# stm_v0_6.net
KiCad netlist of a schematic drawn in EAGLE
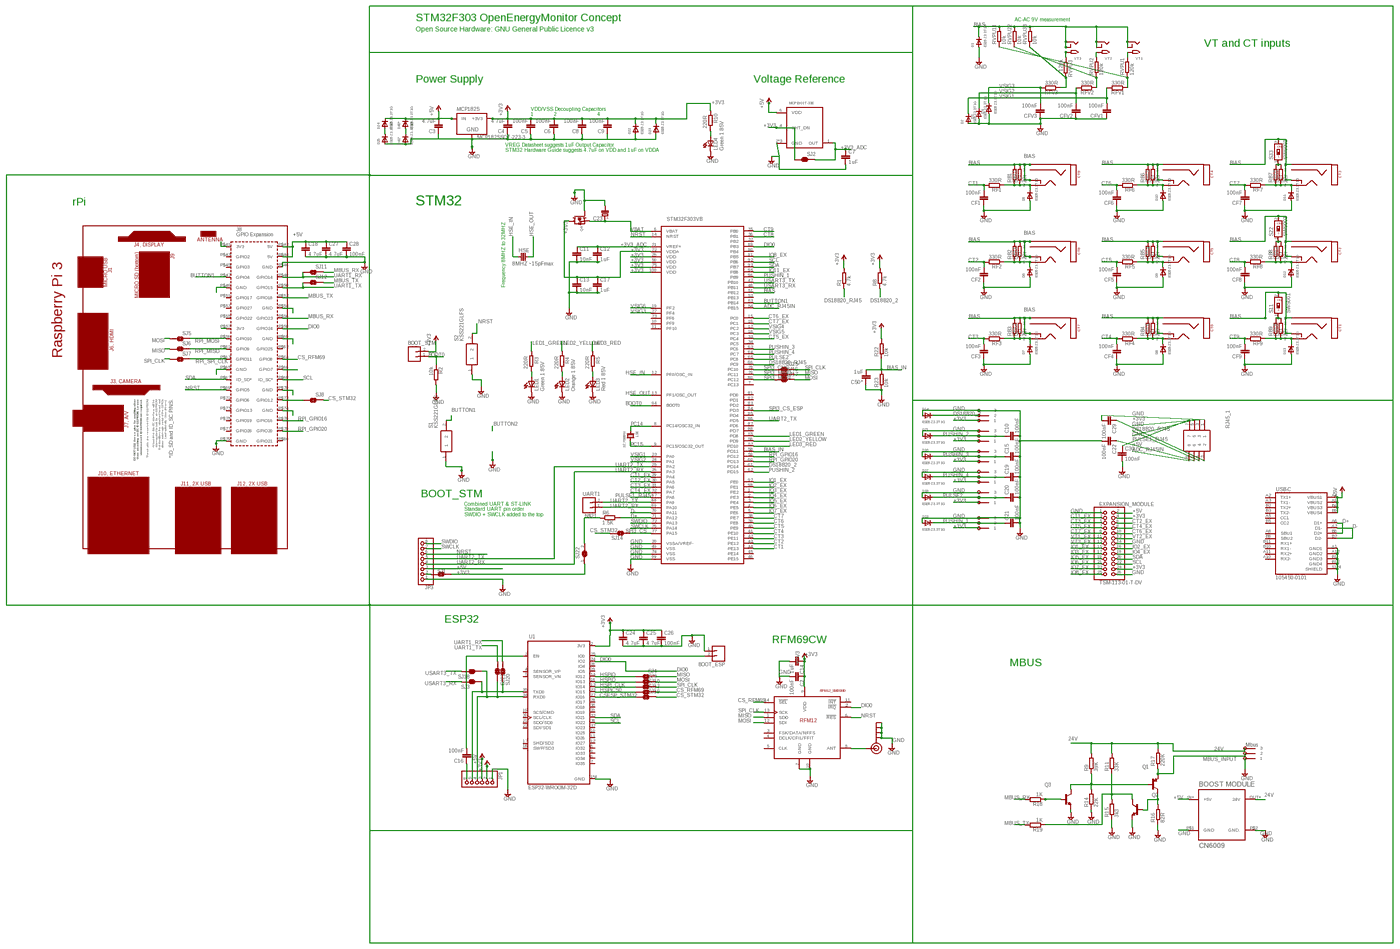
[diagram p0: schematic, sheet 1, overview]
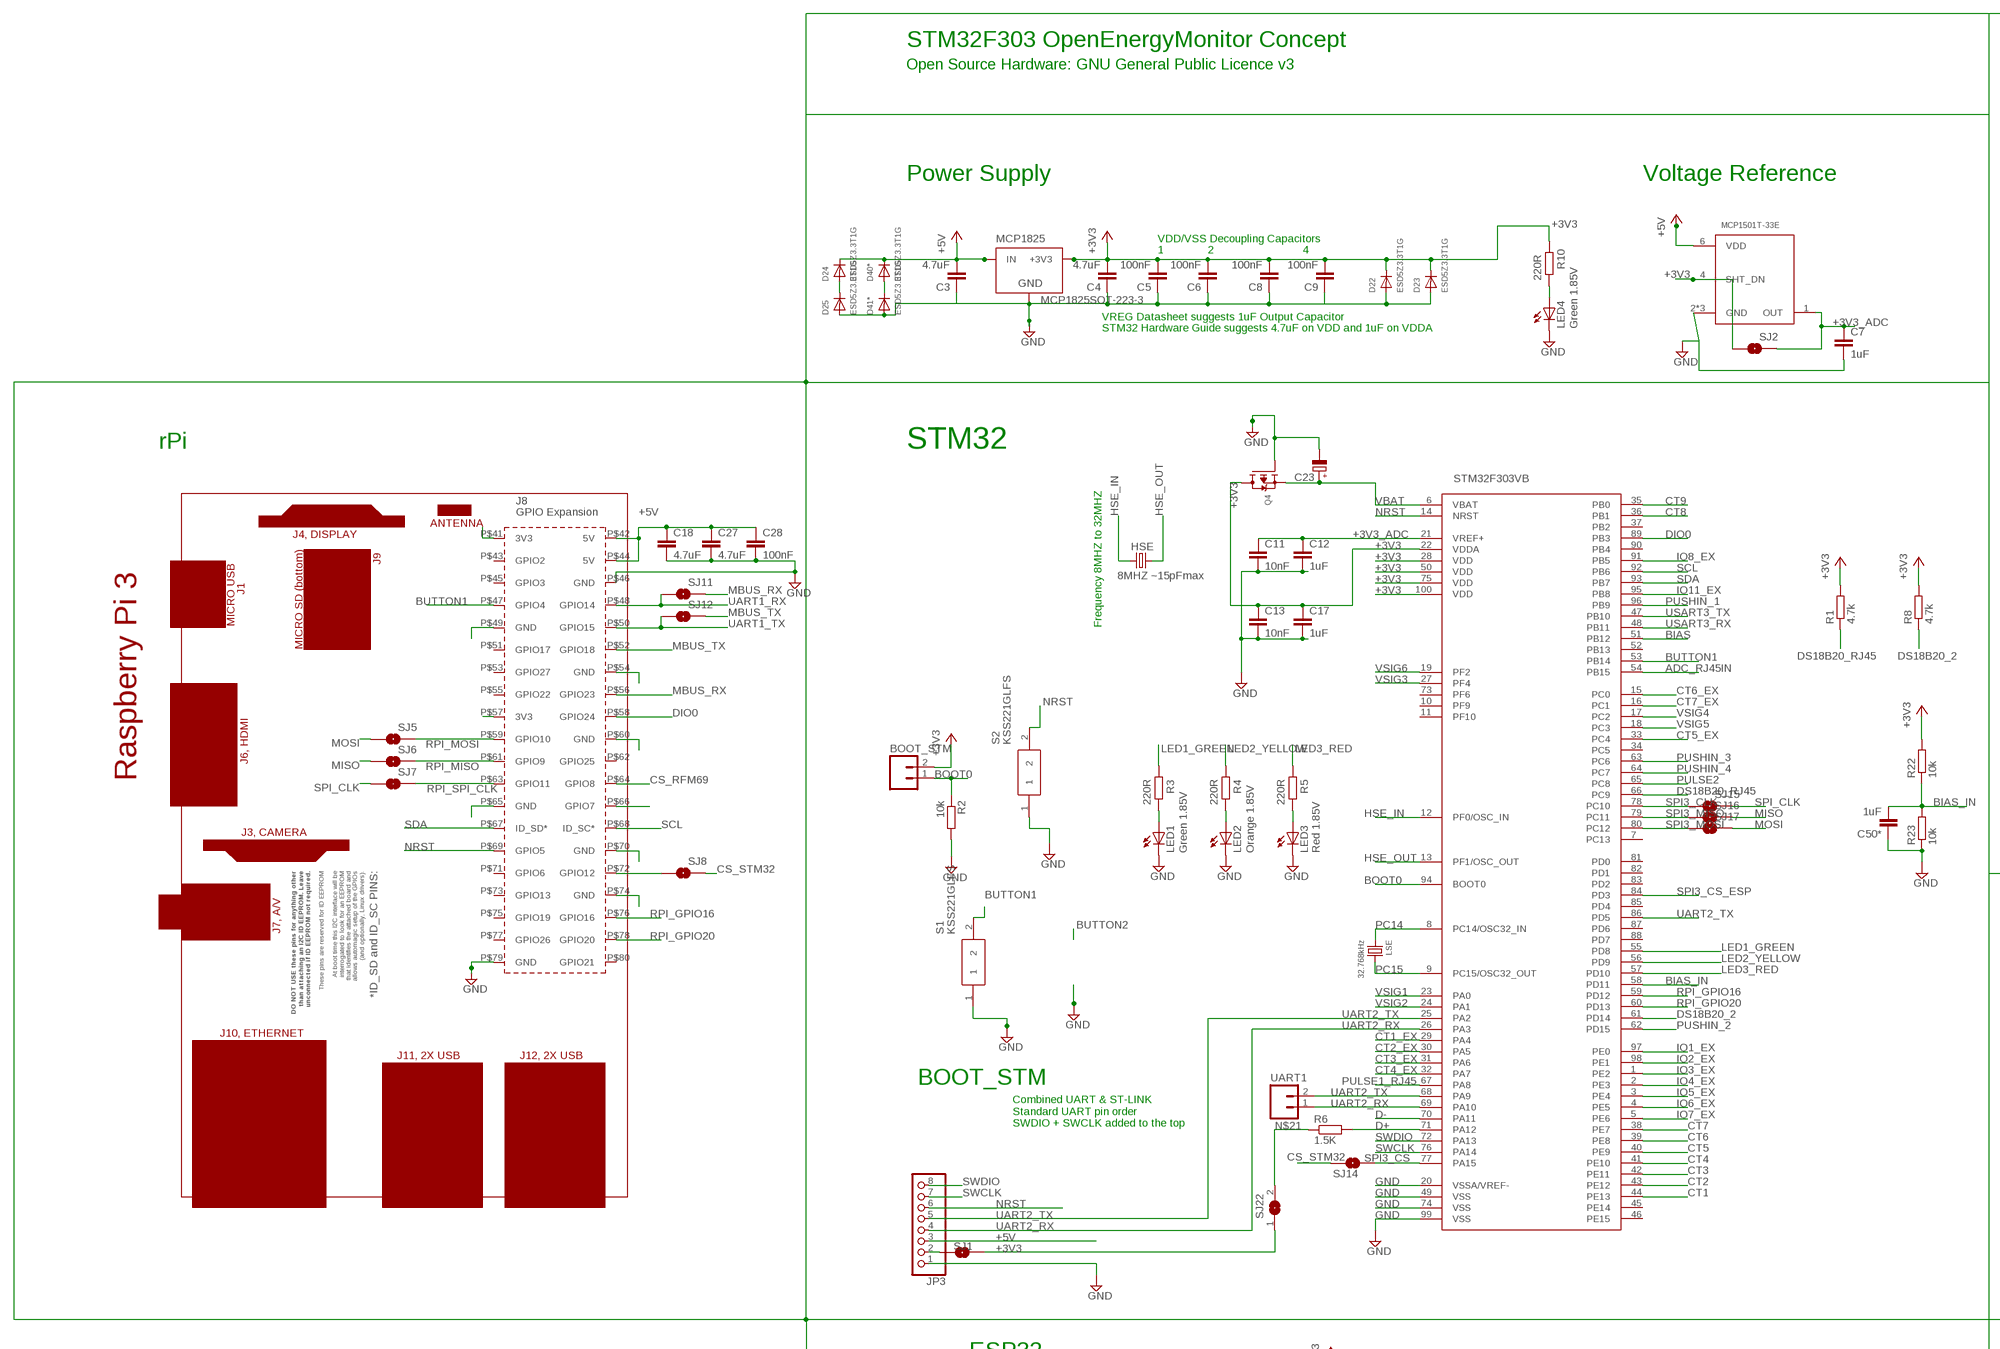
[diagram p1: schematic, sheet 1, part 1 of 4]
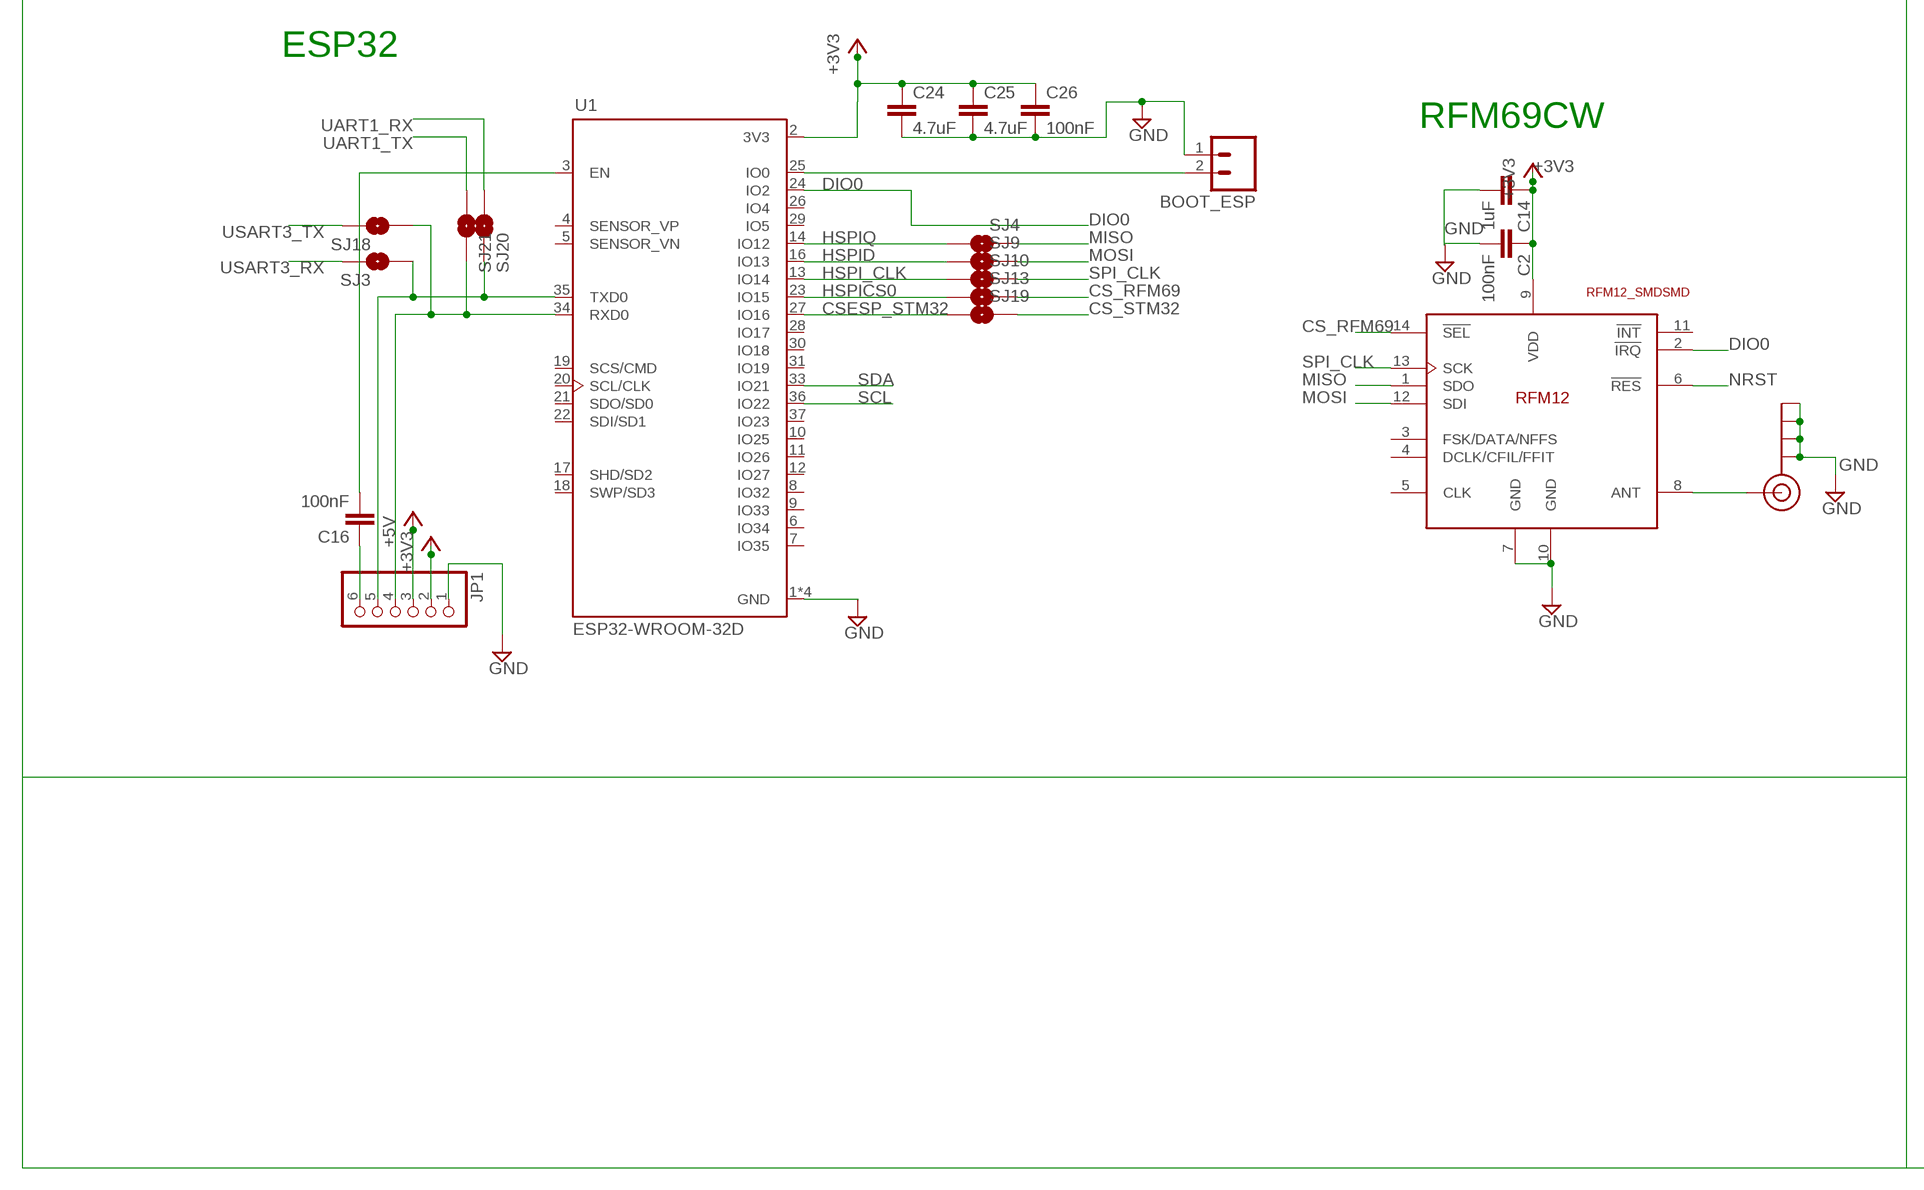
[diagram p2: schematic, sheet 1, part 2 of 4]
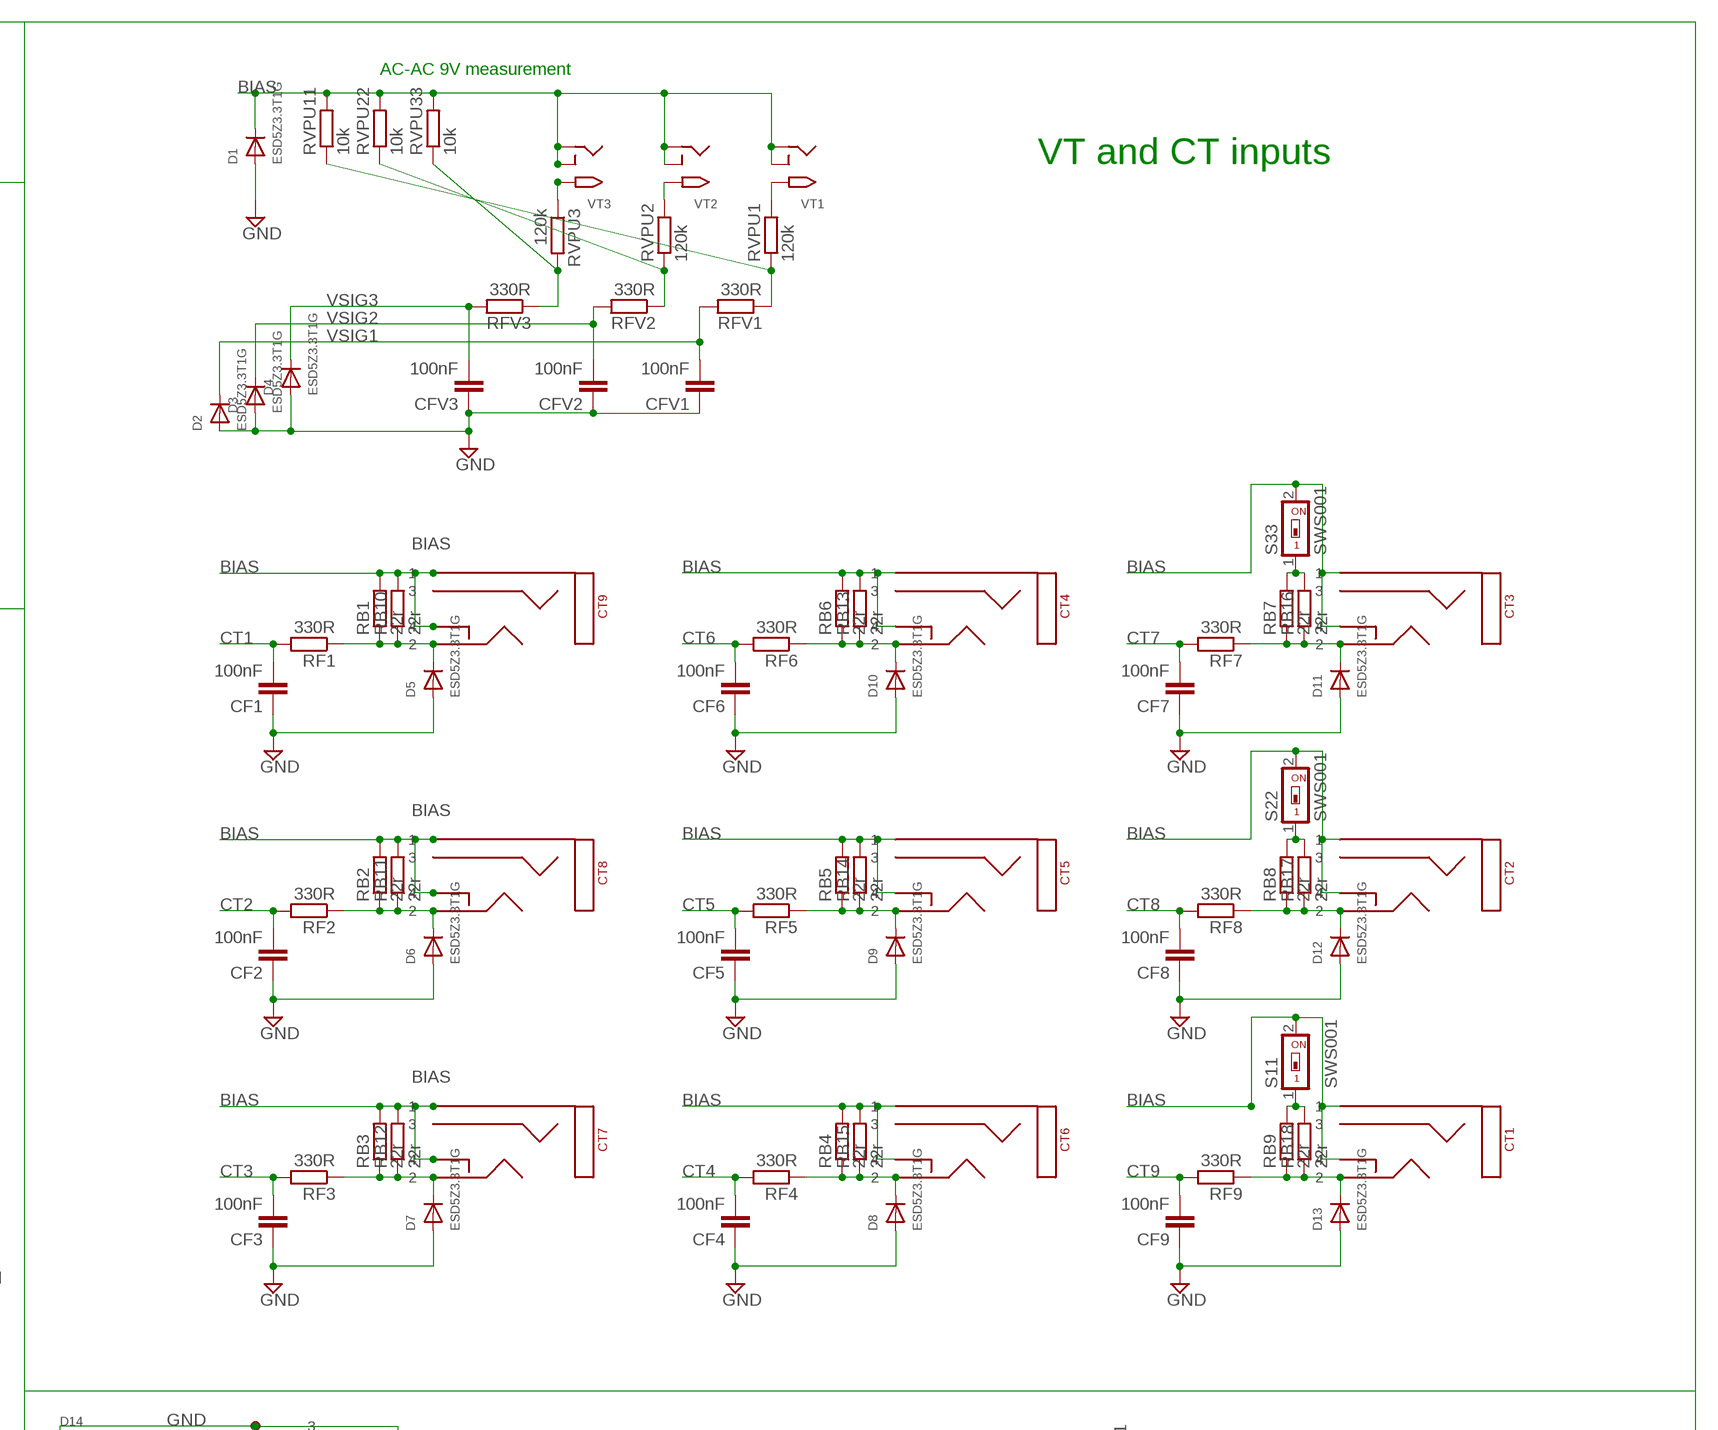
[diagram p3: schematic, sheet 1, part 3 of 4]
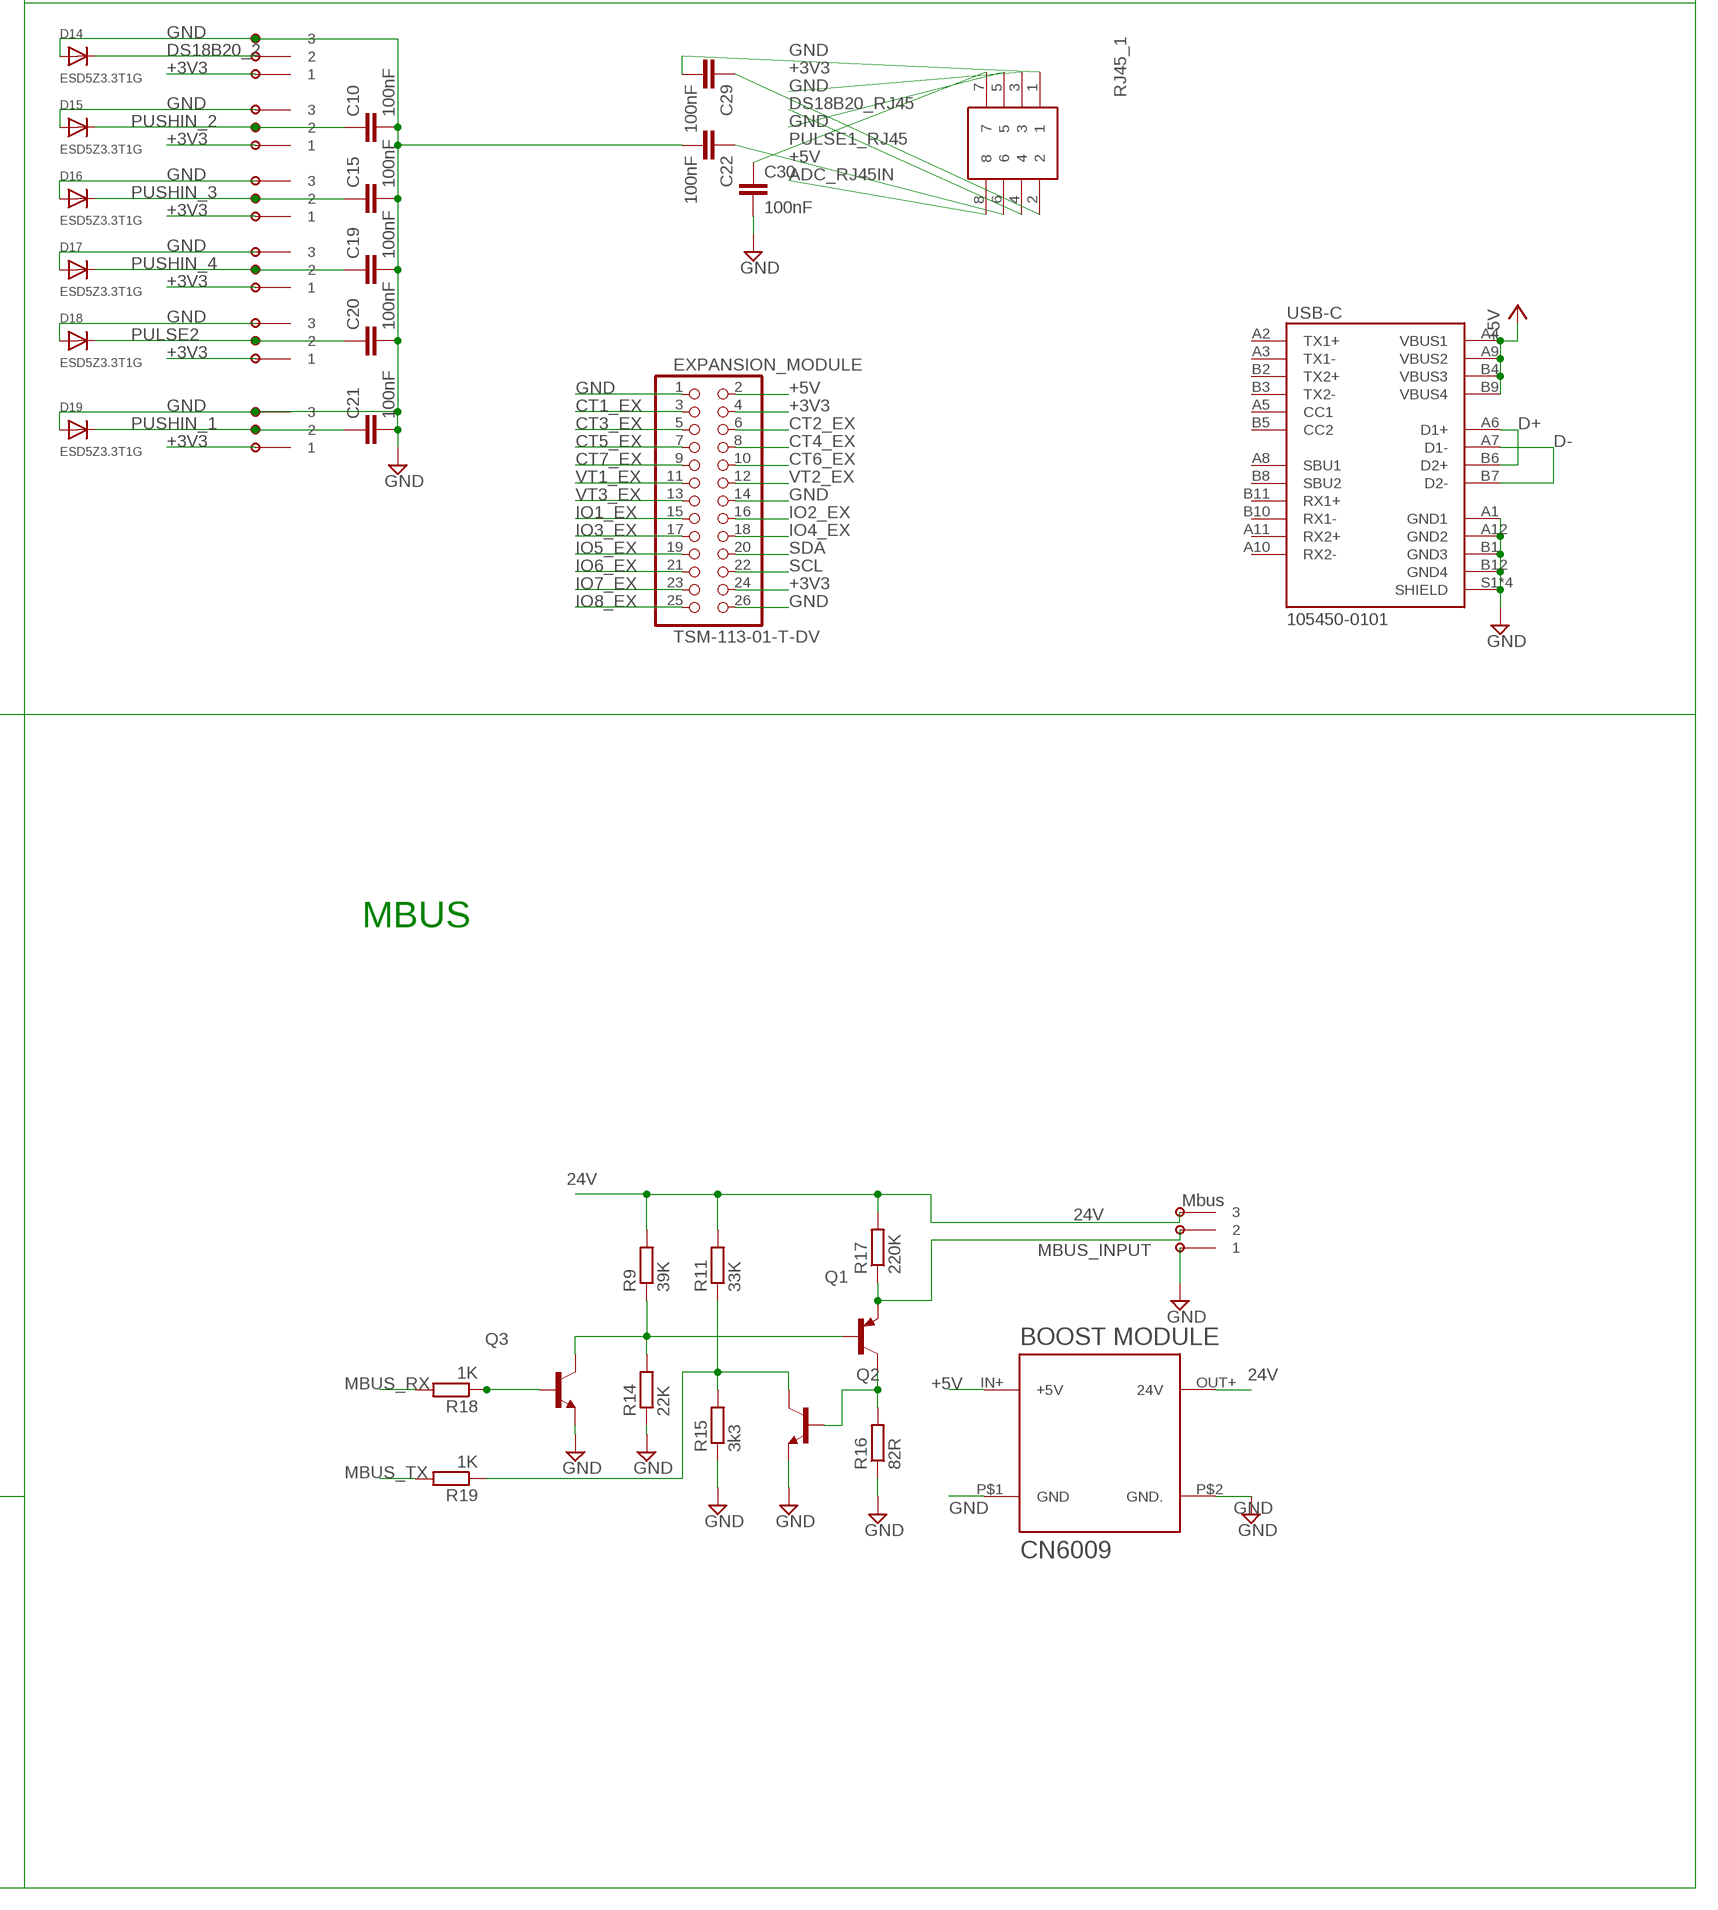
[diagram p4: schematic, sheet 1, part 4 of 4]

(export (version "E")
  (design (tool "Eeschema 10.0.6"))
  (components
    (comp (ref "3POLE_1")
      (value "OMNIMATE_LSF_3COMBICON_SMT_3")
      (footprint "eagle-import:OMNIMATE_LSF_3_SMT")
      (libsource (lib "eagle-import") (part "OMNIMATE_LSF_3COMBICON_SMT_3"))
    )
    (comp (ref "3POLE_2")
      (value "OMNIMATE_LSF_3COMBICON_SMT_3")
      (footprint "eagle-import:OMNIMATE_LSF_3_SMT")
      (libsource (lib "eagle-import") (part "OMNIMATE_LSF_3COMBICON_SMT_3"))
    )
    (comp (ref "3POLE_3")
      (value "OMNIMATE_LSF_3COMBICON_SMT_3")
      (footprint "eagle-import:OMNIMATE_LSF_3_SMT")
      (libsource (lib "eagle-import") (part "OMNIMATE_LSF_3COMBICON_SMT_3"))
    )
    (comp (ref "3POLE_4")
      (value "OMNIMATE_LSF_3COMBICON_SMT_3")
      (footprint "eagle-import:OMNIMATE_LSF_3_SMT")
      (libsource (lib "eagle-import") (part "OMNIMATE_LSF_3COMBICON_SMT_3"))
    )
    (comp (ref "3POLE_5")
      (value "OMNIMATE_LSF_3COMBICON_SMT_3")
      (footprint "eagle-import:OMNIMATE_LSF_3_SMT")
      (libsource (lib "eagle-import") (part "OMNIMATE_LSF_3COMBICON_SMT_3"))
    )
    (comp (ref "3POLE_6")
      (value "OMNIMATE_LSF_3COMBICON_SMT_3")
      (footprint "eagle-import:OMNIMATE_LSF_3_SMT")
      (libsource (lib "eagle-import") (part "OMNIMATE_LSF_3COMBICON_SMT_3"))
    )
    (comp (ref "3POLE_7")
      (value "OMNIMATE_LSF_3COMBICON_SMT_3")
      (footprint "eagle-import:OMNIMATE_LSF_3_SMT")
      (libsource (lib "eagle-import") (part "OMNIMATE_LSF_3COMBICON_SMT_3"))
    )
    (comp (ref "BOOT_ESP")
      (value "M02PTH")
      (footprint "eagle-import:1X02")
      (libsource (lib "eagle-import") (part "M02PTH"))
    )
    (comp (ref "BOOT_STM")
      (value "M02PTH")
      (footprint "eagle-import:1X02")
      (libsource (lib "eagle-import") (part "M02PTH"))
    )
    (comp (ref "C2")
      (value "100nF")
      (footprint "eagle-import:C0603")
      (libsource (lib "eagle-import") (part "resistor_C-EUC0603"))
    )
    (comp (ref "C3")
      (value "4.7uF")
      (footprint "eagle-import:C0805")
      (libsource (lib "eagle-import") (part "C-EUC0805"))
    )
    (comp (ref "C4")
      (value "4.7uF")
      (footprint "eagle-import:C0805")
      (libsource (lib "eagle-import") (part "C-EUC0805"))
    )
    (comp (ref "C5")
      (value "100nF")
      (footprint "eagle-import:C0603")
      (libsource (lib "eagle-import") (part "resistor_C-EUC0603"))
    )
    (comp (ref "C6")
      (value "100nF")
      (footprint "eagle-import:C0603")
      (libsource (lib "eagle-import") (part "resistor_C-EUC0603"))
    )
    (comp (ref "C7")
      (value "1uF")
      (footprint "eagle-import:C0805")
      (libsource (lib "eagle-import") (part "C-EUC0805"))
    )
    (comp (ref "C8")
      (value "100nF")
      (footprint "eagle-import:C0603")
      (libsource (lib "eagle-import") (part "resistor_C-EUC0603"))
    )
    (comp (ref "C9")
      (value "100nF")
      (footprint "eagle-import:C0603")
      (libsource (lib "eagle-import") (part "resistor_C-EUC0603"))
    )
    (comp (ref "C10")
      (value "100nF")
      (footprint "eagle-import:C0603")
      (libsource (lib "eagle-import") (part "resistor_C-EUC0603"))
    )
    (comp (ref "C11")
      (value "10nF")
      (footprint "eagle-import:C0603")
      (libsource (lib "eagle-import") (part "C-EUC0603"))
    )
    (comp (ref "C12")
      (value "1uF")
      (footprint "eagle-import:C0805")
      (libsource (lib "eagle-import") (part "C-EUC0805"))
    )
    (comp (ref "C13")
      (value "10nF")
      (footprint "eagle-import:C0603")
      (libsource (lib "eagle-import") (part "C-EUC0603"))
    )
    (comp (ref "C14")
      (value "1uF")
      (footprint "eagle-import:C0805")
      (libsource (lib "eagle-import") (part "C-EUC0805"))
    )
    (comp (ref "C15")
      (value "100nF")
      (footprint "eagle-import:C0603")
      (libsource (lib "eagle-import") (part "resistor_C-EUC0603"))
    )
    (comp (ref "C16")
      (value "100nF")
      (footprint "eagle-import:C0603")
      (libsource (lib "eagle-import") (part "resistor_C-EUC0603"))
    )
    (comp (ref "C17")
      (value "1uF")
      (footprint "eagle-import:C0805")
      (libsource (lib "eagle-import") (part "C-EUC0805"))
    )
    (comp (ref "C18")
      (value "4.7uF")
      (footprint "eagle-import:C0805")
      (libsource (lib "eagle-import") (part "C-EUC0805"))
    )
    (comp (ref "C19")
      (value "100nF")
      (footprint "eagle-import:C0603")
      (libsource (lib "eagle-import") (part "resistor_C-EUC0603"))
    )
    (comp (ref "C20")
      (value "100nF")
      (footprint "eagle-import:C0603")
      (libsource (lib "eagle-import") (part "resistor_C-EUC0603"))
    )
    (comp (ref "C21")
      (value "100nF")
      (footprint "eagle-import:C0603")
      (libsource (lib "eagle-import") (part "resistor_C-EUC0603"))
    )
    (comp (ref "C22")
      (value "100nF")
      (footprint "eagle-import:C0603")
      (libsource (lib "eagle-import") (part "resistor_C-EUC0603"))
    )
    (comp (ref "C23")
      (value "CPOL-EU153CLV-1010")
      (footprint "eagle-import:153CLV-1010")
      (libsource (lib "eagle-import") (part "CPOL-EU153CLV-1010"))
    )
    (comp (ref "C24")
      (value "4.7uF")
      (footprint "eagle-import:C0805")
      (libsource (lib "eagle-import") (part "C-EUC0805"))
    )
    (comp (ref "C25")
      (value "4.7uF")
      (footprint "eagle-import:C0805")
      (libsource (lib "eagle-import") (part "C-EUC0805"))
    )
    (comp (ref "C26")
      (value "100nF")
      (footprint "eagle-import:C0603")
      (libsource (lib "eagle-import") (part "resistor_C-EUC0603"))
    )
    (comp (ref "C27")
      (value "4.7uF")
      (footprint "eagle-import:C0805")
      (libsource (lib "eagle-import") (part "C-EUC0805"))
    )
    (comp (ref "C28")
      (value "100nF")
      (footprint "eagle-import:C0603")
      (libsource (lib "eagle-import") (part "resistor_C-EUC0603"))
    )
    (comp (ref "C29")
      (value "100nF")
      (footprint "eagle-import:C0603")
      (libsource (lib "eagle-import") (part "resistor_C-EUC0603"))
    )
    (comp (ref "C30")
      (value "100nF")
      (footprint "eagle-import:C0603")
      (libsource (lib "eagle-import") (part "resistor_C-EUC0603"))
    )
    (comp (ref "C50*")
      (value "1uF")
      (footprint "eagle-import:C0603")
      (libsource (lib "eagle-import") (part "C-EUC0603"))
    )
    (comp (ref "CF1")
      (value "100nF")
      (footprint "eagle-import:C0603")
      (libsource (lib "eagle-import") (part "resistor_C-EUC0603"))
    )
    (comp (ref "CF2")
      (value "100nF")
      (footprint "eagle-import:C0603")
      (libsource (lib "eagle-import") (part "resistor_C-EUC0603"))
    )
    (comp (ref "CF3")
      (value "100nF")
      (footprint "eagle-import:C0603")
      (libsource (lib "eagle-import") (part "resistor_C-EUC0603"))
    )
    (comp (ref "CF4")
      (value "100nF")
      (footprint "eagle-import:C0603")
      (libsource (lib "eagle-import") (part "resistor_C-EUC0603"))
    )
    (comp (ref "CF5")
      (value "100nF")
      (footprint "eagle-import:C0603")
      (libsource (lib "eagle-import") (part "resistor_C-EUC0603"))
    )
    (comp (ref "CF6")
      (value "100nF")
      (footprint "eagle-import:C0603")
      (libsource (lib "eagle-import") (part "resistor_C-EUC0603"))
    )
    (comp (ref "CF7")
      (value "100nF")
      (footprint "eagle-import:C0603")
      (libsource (lib "eagle-import") (part "resistor_C-EUC0603"))
    )
    (comp (ref "CF8")
      (value "100nF")
      (footprint "eagle-import:C0603")
      (libsource (lib "eagle-import") (part "resistor_C-EUC0603"))
    )
    (comp (ref "CF9")
      (value "100nF")
      (footprint "eagle-import:C0603")
      (libsource (lib "eagle-import") (part "resistor_C-EUC0603"))
    )
    (comp (ref "CFV1")
      (value "100nF")
      (footprint "eagle-import:C0603")
      (libsource (lib "eagle-import") (part "resistor_C-EUC0603"))
    )
    (comp (ref "CFV2")
      (value "100nF")
      (footprint "eagle-import:C0603")
      (libsource (lib "eagle-import") (part "resistor_C-EUC0603"))
    )
    (comp (ref "CFV3")
      (value "100nF")
      (footprint "eagle-import:C0603")
      (libsource (lib "eagle-import") (part "resistor_C-EUC0603"))
    )
    (comp (ref "CT1")
      (value "STEREO_SMD")
      (footprint "eagle-import:STEREO_SMT")
      (libsource (lib "eagle-import") (part "STEREO_SMD"))
    )
    (comp (ref "CT2")
      (value "STEREO_SMD")
      (footprint "eagle-import:STEREO_SMT")
      (libsource (lib "eagle-import") (part "STEREO_SMD"))
    )
    (comp (ref "CT3")
      (value "STEREO_SMD")
      (footprint "eagle-import:STEREO_SMT")
      (libsource (lib "eagle-import") (part "STEREO_SMD"))
    )
    (comp (ref "CT4")
      (value "STEREO_SMD")
      (footprint "eagle-import:STEREO_SMT")
      (libsource (lib "eagle-import") (part "STEREO_SMD"))
    )
    (comp (ref "CT5")
      (value "STEREO_SMD")
      (footprint "eagle-import:STEREO_SMT")
      (libsource (lib "eagle-import") (part "STEREO_SMD"))
    )
    (comp (ref "CT6")
      (value "STEREO_SMD")
      (footprint "eagle-import:STEREO_SMT")
      (libsource (lib "eagle-import") (part "STEREO_SMD"))
    )
    (comp (ref "CT7")
      (value "STEREO_SMD")
      (footprint "eagle-import:STEREO_SMT")
      (libsource (lib "eagle-import") (part "STEREO_SMD"))
    )
    (comp (ref "CT8")
      (value "STEREO_SMD")
      (footprint "eagle-import:STEREO_SMT")
      (libsource (lib "eagle-import") (part "STEREO_SMD"))
    )
    (comp (ref "CT9")
      (value "STEREO_SMD")
      (footprint "eagle-import:STEREO_SMT")
      (libsource (lib "eagle-import") (part "STEREO_SMD"))
    )
    (comp (ref "D1")
      (value "ESD5Z3.3T1G")
      (footprint "eagle-import:SOD-523")
      (libsource (lib "eagle-import") (part "DIODESOD-523"))
    )
    (comp (ref "D2")
      (value "ESD5Z3.3T1G")
      (footprint "eagle-import:SOD-523")
      (libsource (lib "eagle-import") (part "DIODESOD-523"))
    )
    (comp (ref "D3")
      (value "ESD5Z3.3T1G")
      (footprint "eagle-import:SOD-523")
      (libsource (lib "eagle-import") (part "DIODESOD-523"))
    )
    (comp (ref "D4")
      (value "ESD5Z3.3T1G")
      (footprint "eagle-import:SOD-523")
      (libsource (lib "eagle-import") (part "DIODESOD-523"))
    )
    (comp (ref "D5")
      (value "ESD5Z3.3T1G")
      (footprint "eagle-import:SOD-523")
      (libsource (lib "eagle-import") (part "DIODESOD-523"))
    )
    (comp (ref "D6")
      (value "ESD5Z3.3T1G")
      (footprint "eagle-import:SOD-523")
      (libsource (lib "eagle-import") (part "DIODESOD-523"))
    )
    (comp (ref "D7")
      (value "ESD5Z3.3T1G")
      (footprint "eagle-import:SOD-523")
      (libsource (lib "eagle-import") (part "DIODESOD-523"))
    )
    (comp (ref "D8")
      (value "ESD5Z3.3T1G")
      (footprint "eagle-import:SOD-523")
      (libsource (lib "eagle-import") (part "DIODESOD-523"))
    )
    (comp (ref "D9")
      (value "ESD5Z3.3T1G")
      (footprint "eagle-import:SOD-523")
      (libsource (lib "eagle-import") (part "DIODESOD-523"))
    )
    (comp (ref "D10")
      (value "ESD5Z3.3T1G")
      (footprint "eagle-import:SOD-523")
      (libsource (lib "eagle-import") (part "DIODESOD-523"))
    )
    (comp (ref "D11")
      (value "ESD5Z3.3T1G")
      (footprint "eagle-import:SOD-523")
      (libsource (lib "eagle-import") (part "DIODESOD-523"))
    )
    (comp (ref "D12")
      (value "ESD5Z3.3T1G")
      (footprint "eagle-import:SOD-523")
      (libsource (lib "eagle-import") (part "DIODESOD-523"))
    )
    (comp (ref "D13")
      (value "ESD5Z3.3T1G")
      (footprint "eagle-import:SOD-523")
      (libsource (lib "eagle-import") (part "DIODESOD-523"))
    )
    (comp (ref "D14")
      (value "ESD5Z3.3T1G")
      (footprint "eagle-import:SOD-523")
      (libsource (lib "eagle-import") (part "DIODESOD-523"))
    )
    (comp (ref "D15")
      (value "ESD5Z3.3T1G")
      (footprint "eagle-import:SOD-523")
      (libsource (lib "eagle-import") (part "DIODESOD-523"))
    )
    (comp (ref "D16")
      (value "ESD5Z3.3T1G")
      (footprint "eagle-import:SOD-523")
      (libsource (lib "eagle-import") (part "DIODESOD-523"))
    )
    (comp (ref "D17")
      (value "ESD5Z3.3T1G")
      (footprint "eagle-import:SOD-523")
      (libsource (lib "eagle-import") (part "DIODESOD-523"))
    )
    (comp (ref "D18")
      (value "ESD5Z3.3T1G")
      (footprint "eagle-import:SOD-523")
      (libsource (lib "eagle-import") (part "DIODESOD-523"))
    )
    (comp (ref "D19")
      (value "ESD5Z3.3T1G")
      (footprint "eagle-import:SOD-523")
      (libsource (lib "eagle-import") (part "DIODESOD-523"))
    )
    (comp (ref "D22")
      (value "ESD5Z3.3T1G")
      (footprint "eagle-import:SOD-523")
      (libsource (lib "eagle-import") (part "DIODESOD-523"))
    )
    (comp (ref "D23")
      (value "ESD5Z3.3T1G")
      (footprint "eagle-import:SOD-523")
      (libsource (lib "eagle-import") (part "DIODESOD-523"))
    )
    (comp (ref "D24")
      (value "ESD5Z3.3T1G")
      (footprint "eagle-import:SOD-523")
      (libsource (lib "eagle-import") (part "DIODESOD-523"))
    )
    (comp (ref "D25")
      (value "ESD5Z3.3T1G")
      (footprint "eagle-import:SOD-523")
      (libsource (lib "eagle-import") (part "DIODESOD-523"))
    )
    (comp (ref "D40*")
      (value "ESD5Z3.3T1G")
      (footprint "eagle-import:SOD-523")
      (libsource (lib "eagle-import") (part "DIODESOD-523"))
    )
    (comp (ref "D41*")
      (value "ESD5Z3.3T1G")
      (footprint "eagle-import:SOD-523")
      (libsource (lib "eagle-import") (part "DIODESOD-523"))
    )
    (comp (ref "EXPANSION_MODULE")
      (value "TSM-113-01-T-DV")
      (footprint "eagle-import:2X13_SMT")
      (libsource (lib "eagle-import") (part "PINHD-2X13SMT"))
    )
    (comp (ref "HSE")
      (value "8MHZ ~15pFmax")
      (footprint "eagle-import:CTS406")
      (libsource (lib "eagle-import") (part "CRYSTALCTS406"))
    )
    (comp (ref "J$1")
      (value "SMA_EDGE")
      (footprint "eagle-import:SMA-EDGE")
      (libsource (lib "eagle-import") (part "SMA_EDGE"))
    )
    (comp (ref "JP1")
      (value "PINHD-1X61X06_SMT")
      (footprint "eagle-import:1X06_SMT")
      (libsource (lib "eagle-import") (part "PINHD-1X61X06_SMT"))
    )
    (comp (ref "JP3")
      (value "PINHD-1X81X08_SMT")
      (footprint "eagle-import:1X08_SMT")
      (libsource (lib "eagle-import") (part "PINHD-1X81X08_SMT"))
    )
    (comp (ref "LED1")
      (value "Green 1.85V")
      (footprint "eagle-import:CHIP-LED0805")
      (libsource (lib "eagle-import") (part "LEDCHIP-LED0805"))
    )
    (comp (ref "LED2")
      (value "Orange 1.85V")
      (footprint "eagle-import:CHIP-LED0805")
      (libsource (lib "eagle-import") (part "LEDCHIP-LED0805"))
    )
    (comp (ref "LED3")
      (value "Red 1.85V")
      (footprint "eagle-import:CHIP-LED0805")
      (libsource (lib "eagle-import") (part "LEDCHIP-LED0805"))
    )
    (comp (ref "LED4")
      (value "Green 1.85V")
      (footprint "eagle-import:CHIP-LED0805")
      (libsource (lib "eagle-import") (part "LEDCHIP-LED0805"))
    )
    (comp (ref "LSE")
      (value "32.768kHz")
      (footprint "eagle-import:CRYSTAL_8X3.8")
      (libsource (lib "eagle-import") (part "CRYSTAL8X3.8SMT"))
    )
    (comp (ref "MCP1825")
      (value "MCP1825SOT-223-3")
      (footprint "eagle-import:SOT-223")
      (libsource (lib "eagle-import") (part "MCP1825SOT-223-3"))
    )
    (comp (ref "PCB2")
      (value "RPI3YA")
      (footprint "eagle-import:RPI3MIRROR2")
      (libsource (lib "eagle-import") (part "RPI3YA"))
    )
    (comp (ref "Q1")
      (value "MMBT3906")
      (footprint "eagle-import:SOT23")
      (fields
        (field (name "DIGIKEY_PART_NUMBER") "MMBT3906FSCT-ND")
        (field (name "MANUFACTURER") "ON Semiconductor")
        (field (name "CREATED_BY") "PCB Layout")
      )
      (libsource (lib "eagle-import") (part "MMBT3906"))
    )
    (comp (ref "Q2")
      (value "MMBT3904")
      (footprint "eagle-import:SOT23")
      (fields
        (field (name "DIGIKEY_PART_NUMBER") "MMBT3904FSCT-ND")
        (field (name "MANUFACTURER") "ON Semiconductor")
        (field (name "CREATED_BY") "PCB Layout")
      )
      (libsource (lib "eagle-import") (part "MMBT3904"))
    )
    (comp (ref "Q3")
      (value "MMBT3904")
      (footprint "eagle-import:SOT23")
      (fields
        (field (name "DIGIKEY_PART_NUMBER") "MMBT3904FSCT-ND")
        (field (name "MANUFACTURER") "ON Semiconductor")
        (field (name "CREATED_BY") "PCB Layout")
      )
      (libsource (lib "eagle-import") (part "MMBT3904"))
    )
    (comp (ref "Q4")
      (value "MOSFET-P")
      (footprint "eagle-import:SOT23-R")
      (libsource (lib "eagle-import") (part "MOSFET-P"))
    )
    (comp (ref "R1")
      (value "4.7k")
      (footprint "eagle-import:R0603")
      (libsource (lib "eagle-import") (part "resistor_R-EU_R0603"))
    )
    (comp (ref "R2")
      (value "10k")
      (footprint "eagle-import:R0603")
      (libsource (lib "eagle-import") (part "resistor_R-EU_R0603"))
    )
    (comp (ref "R3")
      (value "220R")
      (footprint "eagle-import:R0603")
      (libsource (lib "eagle-import") (part "R-EU_R0603"))
    )
    (comp (ref "R4")
      (value "220R")
      (footprint "eagle-import:R0603")
      (libsource (lib "eagle-import") (part "R-EU_R0603"))
    )
    (comp (ref "R5")
      (value "220R")
      (footprint "eagle-import:R0603")
      (libsource (lib "eagle-import") (part "R-EU_R0603"))
    )
    (comp (ref "R6")
      (value "1.5K")
      (footprint "eagle-import:R0603")
      (libsource (lib "eagle-import") (part "R-EU_R0603"))
    )
    (comp (ref "R8")
      (value "4.7k")
      (footprint "eagle-import:R0603")
      (libsource (lib "eagle-import") (part "resistor_R-EU_R0603"))
    )
    (comp (ref "R9")
      (value "39K")
      (footprint "eagle-import:R0603")
      (libsource (lib "eagle-import") (part "R-EU_R0603"))
    )
    (comp (ref "R10")
      (value "220R")
      (footprint "eagle-import:R0603")
      (libsource (lib "eagle-import") (part "R-EU_R0603"))
    )
    (comp (ref "R11")
      (value "33K")
      (footprint "eagle-import:R0603")
      (libsource (lib "eagle-import") (part "R-EU_R0603"))
    )
    (comp (ref "R14")
      (value "22K")
      (footprint "eagle-import:R0603")
      (libsource (lib "eagle-import") (part "R-EU_R0603"))
    )
    (comp (ref "R15")
      (value "3k3")
      (footprint "eagle-import:R0603")
      (libsource (lib "eagle-import") (part "R-EU_R0603"))
    )
    (comp (ref "R16")
      (value "82R")
      (footprint "eagle-import:R0603")
      (libsource (lib "eagle-import") (part "R-EU_R0603"))
    )
    (comp (ref "R17")
      (value "220K")
      (footprint "eagle-import:R0603")
      (libsource (lib "eagle-import") (part "R-EU_R0603"))
    )
    (comp (ref "R18")
      (value "1K")
      (footprint "eagle-import:R0603")
      (libsource (lib "eagle-import") (part "R-EU_R0603"))
    )
    (comp (ref "R19")
      (value "1K")
      (footprint "eagle-import:R0603")
      (libsource (lib "eagle-import") (part "R-EU_R0603"))
    )
    (comp (ref "R22")
      (value "10k")
      (footprint "eagle-import:R0603")
      (libsource (lib "eagle-import") (part "resistor_R-EU_R0603"))
    )
    (comp (ref "R23")
      (value "10k")
      (footprint "eagle-import:R0603")
      (libsource (lib "eagle-import") (part "resistor_R-EU_R0603"))
    )
    (comp (ref "RB1")
      (value "22r")
      (footprint "eagle-import:R0603")
      (libsource (lib "eagle-import") (part "resistor_R-EU_R0603"))
    )
    (comp (ref "RB2")
      (value "22r")
      (footprint "eagle-import:R0603")
      (libsource (lib "eagle-import") (part "resistor_R-EU_R0603"))
    )
    (comp (ref "RB3")
      (value "22r")
      (footprint "eagle-import:R0603")
      (libsource (lib "eagle-import") (part "resistor_R-EU_R0603"))
    )
    (comp (ref "RB4")
      (value "22r")
      (footprint "eagle-import:R0603")
      (libsource (lib "eagle-import") (part "resistor_R-EU_R0603"))
    )
    (comp (ref "RB5")
      (value "22r")
      (footprint "eagle-import:R0603")
      (libsource (lib "eagle-import") (part "resistor_R-EU_R0603"))
    )
    (comp (ref "RB6")
      (value "22r")
      (footprint "eagle-import:R0603")
      (libsource (lib "eagle-import") (part "resistor_R-EU_R0603"))
    )
    (comp (ref "RB7")
      (value "22r")
      (footprint "eagle-import:R0603")
      (libsource (lib "eagle-import") (part "resistor_R-EU_R0603"))
    )
    (comp (ref "RB8")
      (value "22r")
      (footprint "eagle-import:R0603")
      (libsource (lib "eagle-import") (part "resistor_R-EU_R0603"))
    )
    (comp (ref "RB9")
      (value "22r")
      (footprint "eagle-import:R0603")
      (libsource (lib "eagle-import") (part "resistor_R-EU_R0603"))
    )
    (comp (ref "RB10")
      (value "22r")
      (footprint "eagle-import:0207_7")
      (libsource (lib "eagle-import") (part "R-EU_0207/7"))
    )
    (comp (ref "RB11")
      (value "22r")
      (footprint "eagle-import:0207_7")
      (libsource (lib "eagle-import") (part "R-EU_0207/7"))
    )
    (comp (ref "RB12")
      (value "22r")
      (footprint "eagle-import:0207_7")
      (libsource (lib "eagle-import") (part "R-EU_0207/7"))
    )
    (comp (ref "RB13")
      (value "22r")
      (footprint "eagle-import:0207_7")
      (libsource (lib "eagle-import") (part "R-EU_0207/7"))
    )
    (comp (ref "RB14")
      (value "22r")
      (footprint "eagle-import:0207_7")
      (libsource (lib "eagle-import") (part "R-EU_0207/7"))
    )
    (comp (ref "RB15")
      (value "22r")
      (footprint "eagle-import:0207_7")
      (libsource (lib "eagle-import") (part "R-EU_0207/7"))
    )
    (comp (ref "RB16")
      (value "22r")
      (footprint "eagle-import:0207_7")
      (libsource (lib "eagle-import") (part "R-EU_0207/7"))
    )
    (comp (ref "RB17")
      (value "22r")
      (footprint "eagle-import:0207_7")
      (libsource (lib "eagle-import") (part "R-EU_0207/7"))
    )
    (comp (ref "RB18")
      (value "22r")
      (footprint "eagle-import:0207_7")
      (libsource (lib "eagle-import") (part "R-EU_0207/7"))
    )
    (comp (ref "RF1")
      (value "330R")
      (footprint "eagle-import:R0603")
      (libsource (lib "eagle-import") (part "resistor_R-EU_R0603"))
    )
    (comp (ref "RF2")
      (value "330R")
      (footprint "eagle-import:R0603")
      (libsource (lib "eagle-import") (part "resistor_R-EU_R0603"))
    )
    (comp (ref "RF3")
      (value "330R")
      (footprint "eagle-import:R0603")
      (libsource (lib "eagle-import") (part "resistor_R-EU_R0603"))
    )
    (comp (ref "RF4")
      (value "330R")
      (footprint "eagle-import:R0603")
      (libsource (lib "eagle-import") (part "resistor_R-EU_R0603"))
    )
    (comp (ref "RF5")
      (value "330R")
      (footprint "eagle-import:R0603")
      (libsource (lib "eagle-import") (part "resistor_R-EU_R0603"))
    )
    (comp (ref "RF6")
      (value "330R")
      (footprint "eagle-import:R0603")
      (libsource (lib "eagle-import") (part "resistor_R-EU_R0603"))
    )
    (comp (ref "RF7")
      (value "330R")
      (footprint "eagle-import:R0603")
      (libsource (lib "eagle-import") (part "resistor_R-EU_R0603"))
    )
    (comp (ref "RF8")
      (value "330R")
      (footprint "eagle-import:R0603")
      (libsource (lib "eagle-import") (part "resistor_R-EU_R0603"))
    )
    (comp (ref "RF9")
      (value "330R")
      (footprint "eagle-import:R0603")
      (libsource (lib "eagle-import") (part "resistor_R-EU_R0603"))
    )
    (comp (ref "RFM69HCW")
      (value "RFM12_SMDSMD")
      (footprint "eagle-import:RFM12")
      (libsource (lib "eagle-import") (part "RFM12_SMDSMD"))
    )
    (comp (ref "RFV1")
      (value "330R")
      (footprint "eagle-import:R0603")
      (libsource (lib "eagle-import") (part "resistor_R-EU_R0603"))
    )
    (comp (ref "RFV2")
      (value "330R")
      (footprint "eagle-import:R0603")
      (libsource (lib "eagle-import") (part "resistor_R-EU_R0603"))
    )
    (comp (ref "RFV3")
      (value "330R")
      (footprint "eagle-import:R0603")
      (libsource (lib "eagle-import") (part "resistor_R-EU_R0603"))
    )
    (comp (ref "RJ45_1")
      (value "95501-6889")
      (footprint "eagle-import:955016889")
      (fields (field (name "MOUSER_PART_NUMBER") "538-95501-6889") (field (name "RS_PART_NUMBER") "3862738"))
      (libsource (lib "eagle-import") (part "95501-6889"))
    )
    (comp (ref "RVPU1")
      (value "120k")
      (footprint "eagle-import:R0603")
      (libsource (lib "eagle-import") (part "resistor_R-EU_R0603"))
    )
    (comp (ref "RVPU2")
      (value "120k")
      (footprint "eagle-import:R0603")
      (libsource (lib "eagle-import") (part "resistor_R-EU_R0603"))
    )
    (comp (ref "RVPU3")
      (value "120k")
      (footprint "eagle-import:R0603")
      (libsource (lib "eagle-import") (part "resistor_R-EU_R0603"))
    )
    (comp (ref "RVPU11")
      (value "10k")
      (footprint "eagle-import:R0603")
      (libsource (lib "eagle-import") (part "resistor_R-EU_R0603"))
    )
    (comp (ref "RVPU22")
      (value "10k")
      (footprint "eagle-import:R0603")
      (libsource (lib "eagle-import") (part "resistor_R-EU_R0603"))
    )
    (comp (ref "RVPU33")
      (value "10k")
      (footprint "eagle-import:R0603")
      (libsource (lib "eagle-import") (part "resistor_R-EU_R0603"))
    )
    (comp (ref "S1")
      (value "KSS221GLFS")
      (footprint "eagle-import:KSS")
      (fields (field (name "RS_PART_NUMBER") "7931689P"))
      (libsource (lib "eagle-import") (part "KSS221GLFS"))
    )
    (comp (ref "S2")
      (value "KSS221GLFS")
      (footprint "eagle-import:KSS")
      (fields (field (name "RS_PART_NUMBER") "7931689P"))
      (libsource (lib "eagle-import") (part "KSS221GLFS"))
    )
    (comp (ref "S11")
      (value "SWS001")
      (footprint "eagle-import:SMS-001")
      (libsource (lib "eagle-import") (part "SWS001"))
    )
    (comp (ref "S22")
      (value "SWS001")
      (footprint "eagle-import:SMS-001")
      (libsource (lib "eagle-import") (part "SWS001"))
    )
    (comp (ref "S33")
      (value "SWS001")
      (footprint "eagle-import:SMS-001")
      (libsource (lib "eagle-import") (part "SWS001"))
    )
    (comp (ref "SJ1")
      (value "SOLDERJUMPERNO")
      (footprint "eagle-import:SJ_2S-NO")
      (libsource (lib "eagle-import") (part "SOLDERJUMPERNO"))
    )
    (comp (ref "SJ2")
      (value "SOLDERJUMPERNO")
      (footprint "eagle-import:SJ_2S-NO")
      (libsource (lib "eagle-import") (part "SOLDERJUMPERNO"))
    )
    (comp (ref "SJ3")
      (value "SOLDERJUMPERNO")
      (footprint "eagle-import:SJ_2S-NO")
      (libsource (lib "eagle-import") (part "SOLDERJUMPERNO"))
    )
    (comp (ref "SJ4")
      (value "SOLDERJUMPERNO")
      (footprint "eagle-import:SJ_2S-NO")
      (libsource (lib "eagle-import") (part "SOLDERJUMPERNO"))
    )
    (comp (ref "SJ5")
      (value "SOLDERJUMPERNO")
      (footprint "eagle-import:SJ_2S-NO")
      (libsource (lib "eagle-import") (part "SOLDERJUMPERNO"))
    )
    (comp (ref "SJ6")
      (value "SOLDERJUMPERNO")
      (footprint "eagle-import:SJ_2S-NO")
      (libsource (lib "eagle-import") (part "SOLDERJUMPERNO"))
    )
    (comp (ref "SJ7")
      (value "SOLDERJUMPERNO")
      (footprint "eagle-import:SJ_2S-NO")
      (libsource (lib "eagle-import") (part "SOLDERJUMPERNO"))
    )
    (comp (ref "SJ8")
      (value "SOLDERJUMPERNO")
      (footprint "eagle-import:SJ_2S-NO")
      (libsource (lib "eagle-import") (part "SOLDERJUMPERNO"))
    )
    (comp (ref "SJ9")
      (value "SOLDERJUMPERNO")
      (footprint "eagle-import:SJ_2S-NO")
      (libsource (lib "eagle-import") (part "SOLDERJUMPERNO"))
    )
    (comp (ref "SJ10")
      (value "SOLDERJUMPERNO")
      (footprint "eagle-import:SJ_2S-NO")
      (libsource (lib "eagle-import") (part "SOLDERJUMPERNO"))
    )
    (comp (ref "SJ11")
      (value "SOLDERJUMPERNO")
      (footprint "eagle-import:SJ_2S-NO")
      (libsource (lib "eagle-import") (part "SOLDERJUMPERNO"))
    )
    (comp (ref "SJ12")
      (value "SOLDERJUMPERNO")
      (footprint "eagle-import:SJ_2S-NO")
      (libsource (lib "eagle-import") (part "SOLDERJUMPERNO"))
    )
    (comp (ref "SJ13")
      (value "SOLDERJUMPERNO")
      (footprint "eagle-import:SJ_2S-NO")
      (libsource (lib "eagle-import") (part "SOLDERJUMPERNO"))
    )
    (comp (ref "SJ14")
      (value "SOLDERJUMPERNO")
      (footprint "eagle-import:SJ_2S-NO")
      (libsource (lib "eagle-import") (part "SOLDERJUMPERNO"))
    )
    (comp (ref "SJ15")
      (value "SOLDERJUMPERNO")
      (footprint "eagle-import:SJ_2S-NO")
      (libsource (lib "eagle-import") (part "SOLDERJUMPERNO"))
    )
    (comp (ref "SJ16")
      (value "SOLDERJUMPERNO")
      (footprint "eagle-import:SJ_2S-NO")
      (libsource (lib "eagle-import") (part "SOLDERJUMPERNO"))
    )
    (comp (ref "SJ17")
      (value "SOLDERJUMPERNO")
      (footprint "eagle-import:SJ_2S-NO")
      (libsource (lib "eagle-import") (part "SOLDERJUMPERNO"))
    )
    (comp (ref "SJ18")
      (value "SOLDERJUMPERNO")
      (footprint "eagle-import:SJ_2S-NO")
      (libsource (lib "eagle-import") (part "SOLDERJUMPERNO"))
    )
    (comp (ref "SJ19")
      (value "SOLDERJUMPERNO")
      (footprint "eagle-import:SJ_2S-NO")
      (libsource (lib "eagle-import") (part "SOLDERJUMPERNO"))
    )
    (comp (ref "SJ20")
      (value "SOLDERJUMPERNO")
      (footprint "eagle-import:SJ_2S-NO")
      (libsource (lib "eagle-import") (part "SOLDERJUMPERNO"))
    )
    (comp (ref "SJ21")
      (value "SOLDERJUMPERNO")
      (footprint "eagle-import:SJ_2S-NO")
      (libsource (lib "eagle-import") (part "SOLDERJUMPERNO"))
    )
    (comp (ref "SJ22")
      (value "SJ-CONCON")
      (footprint "eagle-import:SJ-CON")
      (libsource (lib "eagle-import") (part "SJ-CONCON"))
    )
    (comp (ref "STM32F303VB")
      (value "STM32F303XB")
      (footprint "eagle-import:TQFP100")
      (libsource (lib "eagle-import") (part "STM32F303XB"))
    )
    (comp (ref "U$2")
      (value "BOOST_MODULE")
      (footprint "eagle-import:BOOST")
      (libsource (lib "eagle-import") (part "BOOST_MODULE"))
    )
    (comp (ref "U1")
      (value "ESP32-WROOM-32D")
      (footprint "eagle-import:MODULE_ESP32-WROOM-32D")
      (fields (field (name "MF") "Espressif Systems"))
      (libsource (lib "eagle-import") (part "ESP32-WROOM-32D"))
    )
    (comp (ref "UART1")
      (value "M02PTH")
      (footprint "eagle-import:1X02")
      (libsource (lib "eagle-import") (part "M02PTH"))
    )
    (comp (ref "USB-C")
      (value "105450-0101")
      (footprint "eagle-import:MOLEX_105450-0101")
      (fields (field (name "MF") "Molex"))
      (libsource (lib "eagle-import") (part "105450-0101"))
    )
    (comp (ref "VREF_3V3")
      (value "MCP1501T-33E")
      (footprint "eagle-import:SOT95P280X145-6N")
      (libsource (lib "eagle-import") (part "MCP1501T-33E"))
    )
    (comp (ref "VT1")
      (value "2.1MMJACKSMT")
      (footprint "eagle-import:DCJACK_2MM_SMT")
      (libsource (lib "eagle-import") (part "2.1MMJACKSMT"))
    )
    (comp (ref "VT2")
      (value "2.1MMJACKSMT")
      (footprint "eagle-import:DCJACK_2MM_SMT")
      (libsource (lib "eagle-import") (part "2.1MMJACKSMT"))
    )
    (comp (ref "VT3")
      (value "2.1MMJACKSMT")
      (footprint "eagle-import:DCJACK_2MM_SMT")
      (libsource (lib "eagle-import") (part "2.1MMJACKSMT"))
    )
  )
  (nets
    (net (code "1") (name "+3V3") (class "Default")
      (node (ref "3POLE_1") (pin "P$1") (pinfunction "1_P$1") (pintype "bidirectional"))
      (node (ref "3POLE_2") (pin "P$1") (pinfunction "1_P$1") (pintype "bidirectional"))
      (node (ref "3POLE_3") (pin "P$1") (pinfunction "1_P$1") (pintype "bidirectional"))
      (node (ref "3POLE_4") (pin "P$1") (pinfunction "1_P$1") (pintype "bidirectional"))
      (node (ref "3POLE_5") (pin "P$1") (pinfunction "1_P$1") (pintype "bidirectional"))
      (node (ref "3POLE_6") (pin "P$1") (pinfunction "1_P$1") (pintype "bidirectional"))
      (node (ref "BOOT_STM") (pin "2") (pinfunction "2_2") (pintype "passive"))
      (node (ref "C13") (pin "1") (pinfunction "1_1") (pintype "passive"))
      (node (ref "C14") (pin "1") (pinfunction "1_1") (pintype "passive"))
      (node (ref "C17") (pin "1") (pinfunction "1_1") (pintype "passive"))
      (node (ref "C2") (pin "1") (pinfunction "1_1") (pintype "passive"))
      (node (ref "C24") (pin "1") (pinfunction "1_1") (pintype "passive"))
      (node (ref "C25") (pin "1") (pinfunction "1_1") (pintype "passive"))
      (node (ref "C26") (pin "1") (pinfunction "1_1") (pintype "passive"))
      (node (ref "C29") (pin "1") (pinfunction "1_1") (pintype "passive"))
      (node (ref "C4") (pin "2") (pinfunction "2_2") (pintype "passive"))
      (node (ref "C5") (pin "2") (pinfunction "2_2") (pintype "passive"))
      (node (ref "C6") (pin "2") (pinfunction "2_2") (pintype "passive"))
      (node (ref "C8") (pin "2") (pinfunction "2_2") (pintype "passive"))
      (node (ref "C9") (pin "2") (pinfunction "2_2") (pintype "passive"))
      (node (ref "D22") (pin "K") (pinfunction "C_K") (pintype "passive"))
      (node (ref "D23") (pin "K") (pinfunction "C_K") (pintype "passive"))
      (node (ref "EXPANSION_MODULE") (pin "24") (pinfunction "24_24") (pintype "passive"))
      (node (ref "EXPANSION_MODULE") (pin "4") (pinfunction "4_4") (pintype "passive"))
      (node (ref "JP1") (pin "2") (pinfunction "2_2") (pintype "passive"))
      (node (ref "MCP1825") (pin "3") (pinfunction "+3V3_3") (pintype "power_in"))
      (node (ref "Q4") (pin "3") (pinfunction "D_3") (pintype "passive"))
      (node (ref "R1") (pin "2") (pinfunction "2_2") (pintype "passive"))
      (node (ref "R10") (pin "2") (pinfunction "2_2") (pintype "passive"))
      (node (ref "R22") (pin "2") (pinfunction "2_2") (pintype "passive"))
      (node (ref "R8") (pin "2") (pinfunction "2_2") (pintype "passive"))
      (node (ref "RFM69HCW") (pin "9") (pinfunction "VDD_9") (pintype "power_in"))
      (node (ref "RJ45_1") (pin "2") (pinfunction "2_2") (pintype "bidirectional"))
      (node (ref "SJ1") (pin "2") (pinfunction "2_2") (pintype "passive"))
      (node (ref "SJ2") (pin "1") (pinfunction "1_1") (pintype "passive"))
      (node (ref "SJ22") (pin "1") (pinfunction "1_1") (pintype "passive"))
      (node (ref "STM32F303VB") (pin "100") (pinfunction "VDD_100") (pintype "bidirectional"))
      (node (ref "STM32F303VB") (pin "22") (pinfunction "VDDA_22") (pintype "bidirectional"))
      (node (ref "STM32F303VB") (pin "28") (pinfunction "VDD_28") (pintype "bidirectional"))
      (node (ref "STM32F303VB") (pin "50") (pinfunction "VDD_50") (pintype "bidirectional"))
      (node (ref "STM32F303VB") (pin "75") (pinfunction "VDD_75") (pintype "bidirectional"))
      (node (ref "U1") (pin "2") (pinfunction "3V3_2") (pintype "power_in"))
      (node (ref "VREF_3V3") (pin "4") (pinfunction "SHT_DN_4") (pintype "bidirectional"))
    )
    (net (code "2") (name "+5V") (class "Default")
      (node (ref "C18") (pin "1") (pinfunction "1_1") (pintype "passive"))
      (node (ref "C27") (pin "1") (pinfunction "1_1") (pintype "passive"))
      (node (ref "C28") (pin "1") (pinfunction "1_1") (pintype "passive"))
      (node (ref "C3") (pin "2") (pinfunction "2_2") (pintype "passive"))
      (node (ref "C30") (pin "1") (pinfunction "1_1") (pintype "passive"))
      (node (ref "D24") (pin "K") (pinfunction "C_K") (pintype "passive"))
      (node (ref "D40*") (pin "K") (pinfunction "C_K") (pintype "passive"))
      (node (ref "EXPANSION_MODULE") (pin "2") (pinfunction "2_2") (pintype "passive"))
      (node (ref "JP1") (pin "3") (pinfunction "3_3") (pintype "passive"))
      (node (ref "JP3") (pin "3") (pinfunction "3_3") (pintype "passive"))
      (node (ref "MCP1825") (pin "1") (pinfunction "IN_1") (pintype "power_in"))
      (node (ref "PCB2") (pin "P$42") (pinfunction "5V_P$42") (pintype "bidirectional"))
      (node (ref "PCB2") (pin "P$44") (pinfunction "5V_P$44") (pintype "bidirectional"))
      (node (ref "RJ45_1") (pin "7") (pinfunction "7_7") (pintype "bidirectional"))
      (node (ref "U$2") (pin "IN+") (pinfunction "+5V_IN+") (pintype "bidirectional"))
      (node (ref "USB-C") (pin "A4") (pinfunction "VBUS1_A4") (pintype "passive"))
      (node (ref "USB-C") (pin "A9") (pinfunction "VBUS2_A9") (pintype "passive"))
      (node (ref "USB-C") (pin "B4") (pinfunction "VBUS3_B4") (pintype "passive"))
      (node (ref "USB-C") (pin "B9") (pinfunction "VBUS4_B9") (pintype "passive"))
      (node (ref "VREF_3V3") (pin "6") (pinfunction "VDD_6") (pintype "bidirectional"))
    )
    (net (code "3") (name "/+3V3_ADC") (class "Default")
      (node (ref "C11") (pin "1") (pinfunction "1_1") (pintype "passive"))
      (node (ref "C12") (pin "1") (pinfunction "1_1") (pintype "passive"))
      (node (ref "C7") (pin "1") (pinfunction "1_1") (pintype "passive"))
      (node (ref "SJ2") (pin "2") (pinfunction "2_2") (pintype "passive"))
      (node (ref "STM32F303VB") (pin "21") (pinfunction "VREF+_21") (pintype "bidirectional"))
      (node (ref "VREF_3V3") (pin "1") (pinfunction "OUT_1") (pintype "bidirectional"))
    )
    (net (code "4") (name "/24V") (class "Default")
      (node (ref "3POLE_7") (pin "P$3") (pinfunction "3_P$3") (pintype "bidirectional"))
      (node (ref "R11") (pin "2") (pinfunction "2_2") (pintype "passive"))
      (node (ref "R17") (pin "2") (pinfunction "2_2") (pintype "passive"))
      (node (ref "R9") (pin "2") (pinfunction "2_2") (pintype "passive"))
      (node (ref "U$2") (pin "OUT+") (pinfunction "24V_OUT+") (pintype "bidirectional"))
    )
    (net (code "5") (name "/ADC_RJ45IN") (class "Default")
      (node (ref "RJ45_1") (pin "8") (pinfunction "8_8") (pintype "bidirectional"))
      (node (ref "STM32F303VB") (pin "54") (pinfunction "PB15_54") (pintype "bidirectional"))
    )
    (net (code "6") (name "/BIAS") (class "Default")
      (node (ref "CT1") (pin "P$1") (pinfunction "1_P$1") (pintype "bidirectional"))
      (node (ref "CT1") (pin "P$4") (pinfunction "4_P$4") (pintype "bidirectional"))
      (node (ref "CT2") (pin "P$1") (pinfunction "1_P$1") (pintype "bidirectional"))
      (node (ref "CT2") (pin "P$4") (pinfunction "4_P$4") (pintype "bidirectional"))
      (node (ref "CT3") (pin "P$1") (pinfunction "1_P$1") (pintype "bidirectional"))
      (node (ref "CT3") (pin "P$4") (pinfunction "4_P$4") (pintype "bidirectional"))
      (node (ref "CT4") (pin "P$1") (pinfunction "1_P$1") (pintype "bidirectional"))
      (node (ref "CT4") (pin "P$4") (pinfunction "4_P$4") (pintype "bidirectional"))
      (node (ref "CT5") (pin "P$1") (pinfunction "1_P$1") (pintype "bidirectional"))
      (node (ref "CT5") (pin "P$4") (pinfunction "4_P$4") (pintype "bidirectional"))
      (node (ref "CT6") (pin "P$1") (pinfunction "1_P$1") (pintype "bidirectional"))
      (node (ref "CT6") (pin "P$4") (pinfunction "4_P$4") (pintype "bidirectional"))
      (node (ref "CT7") (pin "P$1") (pinfunction "1_P$1") (pintype "bidirectional"))
      (node (ref "CT7") (pin "P$4") (pinfunction "4_P$4") (pintype "bidirectional"))
      (node (ref "CT8") (pin "P$1") (pinfunction "1_P$1") (pintype "bidirectional"))
      (node (ref "CT8") (pin "P$4") (pinfunction "4_P$4") (pintype "bidirectional"))
      (node (ref "CT9") (pin "P$1") (pinfunction "1_P$1") (pintype "bidirectional"))
      (node (ref "CT9") (pin "P$4") (pinfunction "4_P$4") (pintype "bidirectional"))
      (node (ref "D1") (pin "K") (pinfunction "C_K") (pintype "passive"))
      (node (ref "RB1") (pin "2") (pinfunction "2_2") (pintype "passive"))
      (node (ref "RB10") (pin "2") (pinfunction "2_2") (pintype "passive"))
      (node (ref "RB11") (pin "2") (pinfunction "2_2") (pintype "passive"))
      (node (ref "RB12") (pin "2") (pinfunction "2_2") (pintype "passive"))
      (node (ref "RB13") (pin "2") (pinfunction "2_2") (pintype "passive"))
      (node (ref "RB14") (pin "2") (pinfunction "2_2") (pintype "passive"))
      (node (ref "RB15") (pin "2") (pinfunction "2_2") (pintype "passive"))
      (node (ref "RB2") (pin "2") (pinfunction "2_2") (pintype "passive"))
      (node (ref "RB3") (pin "2") (pinfunction "2_2") (pintype "passive"))
      (node (ref "RB4") (pin "2") (pinfunction "2_2") (pintype "passive"))
      (node (ref "RB5") (pin "2") (pinfunction "2_2") (pintype "passive"))
      (node (ref "RB6") (pin "2") (pinfunction "2_2") (pintype "passive"))
      (node (ref "RVPU11") (pin "2") (pinfunction "2_2") (pintype "passive"))
      (node (ref "RVPU22") (pin "2") (pinfunction "2_2") (pintype "passive"))
      (node (ref "RVPU33") (pin "2") (pinfunction "2_2") (pintype "passive"))
      (node (ref "S11") (pin "2") (pinfunction "2_2") (pintype "passive"))
      (node (ref "S22") (pin "2") (pinfunction "2_2") (pintype "passive"))
      (node (ref "S33") (pin "2") (pinfunction "2_2") (pintype "passive"))
      (node (ref "STM32F303VB") (pin "51") (pinfunction "PB12_51") (pintype "bidirectional"))
      (node (ref "VT1") (pin "GND") (pinfunction "RING_GND") (pintype "bidirectional"))
      (node (ref "VT1") (pin "GNDBREAK") (pinfunction "RING_SW_GNDBREAK") (pintype "bidirectional"))
      (node (ref "VT2") (pin "GND") (pinfunction "RING_GND") (pintype "bidirectional"))
      (node (ref "VT2") (pin "GNDBREAK") (pinfunction "RING_SW_GNDBREAK") (pintype "bidirectional"))
      (node (ref "VT3") (pin "GND") (pinfunction "RING_GND") (pintype "bidirectional"))
      (node (ref "VT3") (pin "GNDBREAK") (pinfunction "RING_SW_GNDBREAK") (pintype "bidirectional"))
    )
    (net (code "7") (name "/BIAS_IN") (class "Default")
      (node (ref "C50*") (pin "2") (pinfunction "2_2") (pintype "passive"))
      (node (ref "R22") (pin "1") (pinfunction "1_1") (pintype "passive"))
      (node (ref "R23") (pin "2") (pinfunction "2_2") (pintype "passive"))
      (node (ref "STM32F303VB") (pin "58") (pinfunction "PD11_58") (pintype "bidirectional"))
    )
    (net (code "8") (name "/BOOT0") (class "Default")
      (node (ref "BOOT_STM") (pin "1") (pinfunction "1_1") (pintype "passive"))
      (node (ref "R2") (pin "1") (pinfunction "1_1") (pintype "passive"))
      (node (ref "STM32F303VB") (pin "94") (pinfunction "BOOT0_94") (pintype "bidirectional"))
    )
    (net (code "9") (name "/BUTTON1") (class "Default")
      (node (ref "PCB2") (pin "P$47") (pinfunction "GPIO4_P$47") (pintype "bidirectional"))
      (node (ref "S1") (pin "2") (pinfunction "2_2") (pintype "bidirectional"))
      (node (ref "STM32F303VB") (pin "53") (pinfunction "PB14_53") (pintype "bidirectional"))
    )
    (net (code "11") (name "/CSESP_STM32") (class "Default")
      (node (ref "SJ19") (pin "1") (pinfunction "1_1") (pintype "passive"))
      (node (ref "U1") (pin "27") (pinfunction "IO16_27") (pintype "bidirectional"))
    )
    (net (code "12") (name "/CS_RFM69") (class "Default")
      (node (ref "PCB2") (pin "P$64") (pinfunction "GPIO8_P$64") (pintype "bidirectional"))
      (node (ref "RFM69HCW") (pin "14") (pinfunction "~{SEL}_14") (pintype "input"))
      (node (ref "SJ13") (pin "2") (pinfunction "2_2") (pintype "passive"))
    )
    (net (code "13") (name "/CS_STM32") (class "Default")
      (node (ref "SJ14") (pin "1") (pinfunction "1_1") (pintype "passive"))
      (node (ref "SJ19") (pin "2") (pinfunction "2_2") (pintype "passive"))
      (node (ref "SJ8") (pin "2") (pinfunction "2_2") (pintype "passive"))
    )
    (net (code "14") (name "/CT1") (class "Default")
      (node (ref "CF1") (pin "2") (pinfunction "2_2") (pintype "passive"))
      (node (ref "RF1") (pin "2") (pinfunction "2_2") (pintype "passive"))
      (node (ref "STM32F303VB") (pin "44") (pinfunction "PE13_44") (pintype "bidirectional"))
    )
    (net (code "15") (name "/CT1_EX") (class "Default")
      (node (ref "EXPANSION_MODULE") (pin "3") (pinfunction "3_3") (pintype "passive"))
      (node (ref "STM32F303VB") (pin "29") (pinfunction "PA4_29") (pintype "bidirectional"))
    )
    (net (code "16") (name "/CT2") (class "Default")
      (node (ref "CF2") (pin "2") (pinfunction "2_2") (pintype "passive"))
      (node (ref "RF2") (pin "2") (pinfunction "2_2") (pintype "passive"))
      (node (ref "STM32F303VB") (pin "43") (pinfunction "PE12_43") (pintype "bidirectional"))
    )
    (net (code "17") (name "/CT2_EX") (class "Default")
      (node (ref "EXPANSION_MODULE") (pin "6") (pinfunction "6_6") (pintype "passive"))
      (node (ref "STM32F303VB") (pin "30") (pinfunction "PA5_30") (pintype "bidirectional"))
    )
    (net (code "18") (name "/CT3") (class "Default")
      (node (ref "CF3") (pin "2") (pinfunction "2_2") (pintype "passive"))
      (node (ref "RF3") (pin "2") (pinfunction "2_2") (pintype "passive"))
      (node (ref "STM32F303VB") (pin "42") (pinfunction "PE11_42") (pintype "bidirectional"))
    )
    (net (code "19") (name "/CT3_EX") (class "Default")
      (node (ref "EXPANSION_MODULE") (pin "5") (pinfunction "5_5") (pintype "passive"))
      (node (ref "STM32F303VB") (pin "31") (pinfunction "PA6_31") (pintype "bidirectional"))
    )
    (net (code "20") (name "/CT4") (class "Default")
      (node (ref "CF4") (pin "2") (pinfunction "2_2") (pintype "passive"))
      (node (ref "RF4") (pin "2") (pinfunction "2_2") (pintype "passive"))
      (node (ref "STM32F303VB") (pin "41") (pinfunction "PE10_41") (pintype "bidirectional"))
    )
    (net (code "21") (name "/CT4_EX") (class "Default")
      (node (ref "EXPANSION_MODULE") (pin "8") (pinfunction "8_8") (pintype "passive"))
      (node (ref "STM32F303VB") (pin "32") (pinfunction "PA7_32") (pintype "bidirectional"))
    )
    (net (code "22") (name "/CT5") (class "Default")
      (node (ref "CF5") (pin "2") (pinfunction "2_2") (pintype "passive"))
      (node (ref "RF5") (pin "2") (pinfunction "2_2") (pintype "passive"))
      (node (ref "STM32F303VB") (pin "40") (pinfunction "PE9_40") (pintype "bidirectional"))
    )
    (net (code "23") (name "/CT5_EX") (class "Default")
      (node (ref "EXPANSION_MODULE") (pin "7") (pinfunction "7_7") (pintype "passive"))
      (node (ref "STM32F303VB") (pin "33") (pinfunction "PC4_33") (pintype "bidirectional"))
    )
    (net (code "24") (name "/CT6") (class "Default")
      (node (ref "CF6") (pin "2") (pinfunction "2_2") (pintype "passive"))
      (node (ref "RF6") (pin "2") (pinfunction "2_2") (pintype "passive"))
      (node (ref "STM32F303VB") (pin "39") (pinfunction "PE8_39") (pintype "bidirectional"))
    )
    (net (code "25") (name "/CT6_EX") (class "Default")
      (node (ref "EXPANSION_MODULE") (pin "10") (pinfunction "10_10") (pintype "passive"))
      (node (ref "STM32F303VB") (pin "15") (pinfunction "PC0_15") (pintype "bidirectional"))
    )
    (net (code "26") (name "/CT7") (class "Default")
      (node (ref "CF7") (pin "2") (pinfunction "2_2") (pintype "passive"))
      (node (ref "RF7") (pin "2") (pinfunction "2_2") (pintype "passive"))
      (node (ref "STM32F303VB") (pin "38") (pinfunction "PE7_38") (pintype "bidirectional"))
    )
    (net (code "27") (name "/CT7_EX") (class "Default")
      (node (ref "EXPANSION_MODULE") (pin "9") (pinfunction "9_9") (pintype "passive"))
      (node (ref "STM32F303VB") (pin "16") (pinfunction "PC1_16") (pintype "bidirectional"))
    )
    (net (code "28") (name "/CT8") (class "Default")
      (node (ref "CF8") (pin "2") (pinfunction "2_2") (pintype "passive"))
      (node (ref "RF8") (pin "2") (pinfunction "2_2") (pintype "passive"))
      (node (ref "STM32F303VB") (pin "36") (pinfunction "PB1_36") (pintype "bidirectional"))
    )
    (net (code "29") (name "/CT9") (class "Default")
      (node (ref "CF9") (pin "2") (pinfunction "2_2") (pintype "passive"))
      (node (ref "RF9") (pin "2") (pinfunction "2_2") (pintype "passive"))
      (node (ref "STM32F303VB") (pin "35") (pinfunction "PB0_35") (pintype "bidirectional"))
    )
    (net (code "30") (name "/D+") (class "Default")
      (node (ref "R6") (pin "2") (pinfunction "2_2") (pintype "passive"))
      (node (ref "STM32F303VB") (pin "71") (pinfunction "PA12_71") (pintype "bidirectional"))
      (node (ref "USB-C") (pin "A6") (pinfunction "D1+_A6") (pintype "passive"))
      (node (ref "USB-C") (pin "B6") (pinfunction "D2+_B6") (pintype "passive"))
    )
    (net (code "31") (name "/D-") (class "Default")
      (node (ref "STM32F303VB") (pin "70") (pinfunction "PA11_70") (pintype "bidirectional"))
      (node (ref "USB-C") (pin "A7") (pinfunction "D1-_A7") (pintype "passive"))
      (node (ref "USB-C") (pin "B7") (pinfunction "D2-_B7") (pintype "passive"))
    )
    (net (code "32") (name "/DIO0") (class "Default")
      (node (ref "PCB2") (pin "P$58") (pinfunction "GPIO24_P$58") (pintype "bidirectional"))
      (node (ref "RFM69HCW") (pin "2") (pinfunction "~{IRQ}_2") (pintype "output"))
      (node (ref "STM32F303VB") (pin "89") (pinfunction "PB3_89") (pintype "bidirectional"))
      (node (ref "U1") (pin "24") (pinfunction "IO2_24") (pintype "bidirectional"))
    )
    (net (code "33") (name "/DS18B20_2") (class "Default")
      (node (ref "3POLE_1") (pin "P$2") (pinfunction "2_P$2") (pintype "bidirectional"))
      (node (ref "D14") (pin "K") (pinfunction "C_K") (pintype "passive"))
      (node (ref "R8") (pin "1") (pinfunction "1_1") (pintype "passive"))
      (node (ref "STM32F303VB") (pin "61") (pinfunction "PD14_61") (pintype "bidirectional"))
    )
    (net (code "34") (name "/DS18B20_RJ45") (class "Default")
      (node (ref "R1") (pin "1") (pinfunction "1_1") (pintype "passive"))
      (node (ref "RJ45_1") (pin "4") (pinfunction "4_4") (pintype "bidirectional"))
      (node (ref "STM32F303VB") (pin "66") (pinfunction "PC9_66") (pintype "bidirectional"))
    )
    (net (code "35") (name "/HSE_IN") (class "Default")
      (node (ref "HSE") (pin "1") (pinfunction "1_1") (pintype "passive"))
      (node (ref "STM32F303VB") (pin "12") (pinfunction "PF0/OSC_IN_12") (pintype "bidirectional"))
    )
    (net (code "36") (name "/HSE_OUT") (class "Default")
      (node (ref "HSE") (pin "3") (pinfunction "2_3") (pintype "passive"))
      (node (ref "STM32F303VB") (pin "13") (pinfunction "PF1/OSC_OUT_13") (pintype "bidirectional"))
    )
    (net (code "37") (name "/HSPICS0") (class "Default")
      (node (ref "SJ13") (pin "1") (pinfunction "1_1") (pintype "passive"))
      (node (ref "U1") (pin "23") (pinfunction "IO15_23") (pintype "bidirectional"))
    )
    (net (code "38") (name "/HSPID") (class "Default")
      (node (ref "SJ9") (pin "1") (pinfunction "1_1") (pintype "passive"))
      (node (ref "U1") (pin "16") (pinfunction "IO13_16") (pintype "bidirectional"))
    )
    (net (code "39") (name "/HSPIQ") (class "Default")
      (node (ref "SJ4") (pin "1") (pinfunction "1_1") (pintype "passive"))
      (node (ref "U1") (pin "14") (pinfunction "IO12_14") (pintype "bidirectional"))
    )
    (net (code "40") (name "/HSPI_CLK") (class "Default")
      (node (ref "SJ10") (pin "1") (pinfunction "1_1") (pintype "passive"))
      (node (ref "U1") (pin "13") (pinfunction "IO14_13") (pintype "bidirectional"))
    )
    (net (code "41") (name "/IO1_EX") (class "Default")
      (node (ref "EXPANSION_MODULE") (pin "15") (pinfunction "15_15") (pintype "passive"))
      (node (ref "STM32F303VB") (pin "97") (pinfunction "PE0_97") (pintype "bidirectional"))
    )
    (net (code "42") (name "/IO2_EX") (class "Default")
      (node (ref "EXPANSION_MODULE") (pin "16") (pinfunction "16_16") (pintype "passive"))
      (node (ref "STM32F303VB") (pin "98") (pinfunction "PE1_98") (pintype "bidirectional"))
    )
    (net (code "43") (name "/IO3_EX") (class "Default")
      (node (ref "EXPANSION_MODULE") (pin "17") (pinfunction "17_17") (pintype "passive"))
      (node (ref "STM32F303VB") (pin "1") (pinfunction "PE2_1") (pintype "bidirectional"))
    )
    (net (code "44") (name "/IO4_EX") (class "Default")
      (node (ref "EXPANSION_MODULE") (pin "18") (pinfunction "18_18") (pintype "passive"))
      (node (ref "STM32F303VB") (pin "2") (pinfunction "PE3_2") (pintype "bidirectional"))
    )
    (net (code "45") (name "/IO5_EX") (class "Default")
      (node (ref "EXPANSION_MODULE") (pin "19") (pinfunction "19_19") (pintype "passive"))
      (node (ref "STM32F303VB") (pin "3") (pinfunction "PE4_3") (pintype "bidirectional"))
    )
    (net (code "46") (name "/IO6_EX") (class "Default")
      (node (ref "EXPANSION_MODULE") (pin "21") (pinfunction "21_21") (pintype "passive"))
      (node (ref "STM32F303VB") (pin "4") (pinfunction "PE5_4") (pintype "bidirectional"))
    )
    (net (code "47") (name "/IO7_EX") (class "Default")
      (node (ref "EXPANSION_MODULE") (pin "23") (pinfunction "23_23") (pintype "passive"))
      (node (ref "STM32F303VB") (pin "5") (pinfunction "PE6_5") (pintype "bidirectional"))
    )
    (net (code "48") (name "/IO8_EX") (class "Default")
      (node (ref "EXPANSION_MODULE") (pin "25") (pinfunction "25_25") (pintype "passive"))
      (node (ref "STM32F303VB") (pin "91") (pinfunction "PB5_91") (pintype "bidirectional"))
    )
    (net (code "49") (name "/IO11_EX") (class "Default")
      (node (ref "STM32F303VB") (pin "95") (pinfunction "PB8_95") (pintype "bidirectional"))
    )
    (net (code "50") (name "/LED1_GREEN") (class "Default")
      (node (ref "R3") (pin "2") (pinfunction "2_2") (pintype "passive"))
      (node (ref "STM32F303VB") (pin "55") (pinfunction "PD8_55") (pintype "bidirectional"))
    )
    (net (code "51") (name "/LED2_YELLOW") (class "Default")
      (node (ref "R4") (pin "2") (pinfunction "2_2") (pintype "passive"))
      (node (ref "STM32F303VB") (pin "56") (pinfunction "PD9_56") (pintype "bidirectional"))
    )
    (net (code "52") (name "/LED3_RED") (class "Default")
      (node (ref "R5") (pin "2") (pinfunction "2_2") (pintype "passive"))
      (node (ref "STM32F303VB") (pin "57") (pinfunction "PD10_57") (pintype "bidirectional"))
    )
    (net (code "53") (name "/MBUS_INPUT") (class "Default")
      (node (ref "3POLE_7") (pin "P$2") (pinfunction "2_P$2") (pintype "bidirectional"))
      (node (ref "Q1") (pin "2") (pinfunction "E_2") (pintype "passive"))
      (node (ref "R17") (pin "1") (pinfunction "1_1") (pintype "passive"))
    )
    (net (code "54") (name "/MBUS_RX") (class "Default")
      (node (ref "PCB2") (pin "P$56") (pinfunction "GPIO23_P$56") (pintype "bidirectional"))
      (node (ref "R18") (pin "2") (pinfunction "2_2") (pintype "passive"))
      (node (ref "SJ11") (pin "2") (pinfunction "2_2") (pintype "passive"))
    )
    (net (code "55") (name "/MBUS_TX") (class "Default")
      (node (ref "PCB2") (pin "P$52") (pinfunction "GPIO18_P$52") (pintype "bidirectional"))
      (node (ref "R19") (pin "2") (pinfunction "2_2") (pintype "passive"))
      (node (ref "SJ12") (pin "2") (pinfunction "2_2") (pintype "passive"))
    )
    (net (code "56") (name "/MISO") (class "Default")
      (node (ref "RFM69HCW") (pin "1") (pinfunction "SDO_1") (pintype "output"))
      (node (ref "SJ16") (pin "2") (pinfunction "2_2") (pintype "passive"))
      (node (ref "SJ4") (pin "2") (pinfunction "2_2") (pintype "passive"))
      (node (ref "SJ6") (pin "1") (pinfunction "1_1") (pintype "passive"))
    )
    (net (code "57") (name "/MOSI") (class "Default")
      (node (ref "RFM69HCW") (pin "12") (pinfunction "SDI_12") (pintype "input"))
      (node (ref "SJ17") (pin "2") (pinfunction "2_2") (pintype "passive"))
      (node (ref "SJ5") (pin "1") (pinfunction "1_1") (pintype "passive"))
      (node (ref "SJ9") (pin "2") (pinfunction "2_2") (pintype "passive"))
    )
    (net (code "58") (name "/N$21") (class "Default")
      (node (ref "R6") (pin "1") (pinfunction "1_1") (pintype "passive"))
      (node (ref "SJ22") (pin "2") (pinfunction "2_2") (pintype "passive"))
    )
    (net (code "59") (name "/NRST") (class "Default")
      (node (ref "JP3") (pin "6") (pinfunction "6_6") (pintype "passive"))
      (node (ref "PCB2") (pin "P$69") (pinfunction "GPIO5_P$69") (pintype "bidirectional"))
      (node (ref "RFM69HCW") (pin "6") (pinfunction "~{RES}_6") (pintype "bidirectional"))
      (node (ref "S2") (pin "2") (pinfunction "2_2") (pintype "bidirectional"))
      (node (ref "STM32F303VB") (pin "14") (pinfunction "NRST_14") (pintype "bidirectional"))
    )
    (net (code "60") (name "/PC14") (class "Default")
      (node (ref "LSE") (pin "P$1") (pinfunction "1_P$1") (pintype "passive"))
      (node (ref "STM32F303VB") (pin "8") (pinfunction "PC14/OSC32_IN_8") (pintype "bidirectional"))
    )
    (net (code "61") (name "/PC15") (class "Default")
      (node (ref "LSE") (pin "P$4") (pinfunction "2_P$4") (pintype "passive"))
      (node (ref "STM32F303VB") (pin "9") (pinfunction "PC15/OSC32_OUT_9") (pintype "bidirectional"))
    )
    (net (code "62") (name "/PULSE1_RJ45") (class "Default")
      (node (ref "C22") (pin "1") (pinfunction "1_1") (pintype "passive"))
      (node (ref "RJ45_1") (pin "6") (pinfunction "6_6") (pintype "bidirectional"))
      (node (ref "STM32F303VB") (pin "67") (pinfunction "PA8_67") (pintype "bidirectional"))
    )
    (net (code "63") (name "/PULSE2") (class "Default")
      (node (ref "3POLE_5") (pin "P$2") (pinfunction "2_P$2") (pintype "bidirectional"))
      (node (ref "C20") (pin "1") (pinfunction "1_1") (pintype "passive"))
      (node (ref "D18") (pin "K") (pinfunction "C_K") (pintype "passive"))
      (node (ref "STM32F303VB") (pin "65") (pinfunction "PC8_65") (pintype "bidirectional"))
    )
    (net (code "64") (name "/PUSHIN_1") (class "Default")
      (node (ref "3POLE_6") (pin "P$2") (pinfunction "2_P$2") (pintype "bidirectional"))
      (node (ref "C21") (pin "1") (pinfunction "1_1") (pintype "passive"))
      (node (ref "D19") (pin "K") (pinfunction "C_K") (pintype "passive"))
      (node (ref "STM32F303VB") (pin "96") (pinfunction "PB9_96") (pintype "bidirectional"))
    )
    (net (code "65") (name "/PUSHIN_2") (class "Default")
      (node (ref "3POLE_2") (pin "P$2") (pinfunction "2_P$2") (pintype "bidirectional"))
      (node (ref "C10") (pin "1") (pinfunction "1_1") (pintype "passive"))
      (node (ref "D15") (pin "K") (pinfunction "C_K") (pintype "passive"))
      (node (ref "STM32F303VB") (pin "62") (pinfunction "PD15_62") (pintype "bidirectional"))
    )
    (net (code "66") (name "/PUSHIN_3") (class "Default")
      (node (ref "3POLE_3") (pin "P$2") (pinfunction "2_P$2") (pintype "bidirectional"))
      (node (ref "C15") (pin "1") (pinfunction "1_1") (pintype "passive"))
      (node (ref "D16") (pin "K") (pinfunction "C_K") (pintype "passive"))
      (node (ref "STM32F303VB") (pin "63") (pinfunction "PC6_63") (pintype "bidirectional"))
    )
    (net (code "67") (name "/PUSHIN_4") (class "Default")
      (node (ref "3POLE_4") (pin "P$2") (pinfunction "2_P$2") (pintype "bidirectional"))
      (node (ref "C19") (pin "1") (pinfunction "1_1") (pintype "passive"))
      (node (ref "D17") (pin "K") (pinfunction "C_K") (pintype "passive"))
      (node (ref "STM32F303VB") (pin "64") (pinfunction "PC7_64") (pintype "bidirectional"))
    )
    (net (code "68") (name "/RPI_GPIO16") (class "Default")
      (node (ref "PCB2") (pin "P$76") (pinfunction "GPIO16_P$76") (pintype "bidirectional"))
      (node (ref "STM32F303VB") (pin "59") (pinfunction "PD12_59") (pintype "bidirectional"))
    )
    (net (code "69") (name "/RPI_GPIO20") (class "Default")
      (node (ref "PCB2") (pin "P$78") (pinfunction "GPIO20_P$78") (pintype "bidirectional"))
      (node (ref "STM32F303VB") (pin "60") (pinfunction "PD13_60") (pintype "bidirectional"))
    )
    (net (code "70") (name "/RPI_MISO") (class "Default")
      (node (ref "PCB2") (pin "P$61") (pinfunction "GPIO9_P$61") (pintype "bidirectional"))
      (node (ref "SJ6") (pin "2") (pinfunction "2_2") (pintype "passive"))
    )
    (net (code "71") (name "/RPI_MOSI") (class "Default")
      (node (ref "PCB2") (pin "P$59") (pinfunction "GPIO10_P$59") (pintype "bidirectional"))
      (node (ref "SJ5") (pin "2") (pinfunction "2_2") (pintype "passive"))
    )
    (net (code "72") (name "/RPI_SPI_CLK") (class "Default")
      (node (ref "PCB2") (pin "P$63") (pinfunction "GPIO11_P$63") (pintype "bidirectional"))
      (node (ref "SJ7") (pin "2") (pinfunction "2_2") (pintype "passive"))
    )
    (net (code "73") (name "/SCL") (class "Default")
      (node (ref "EXPANSION_MODULE") (pin "22") (pinfunction "22_22") (pintype "passive"))
      (node (ref "PCB2") (pin "P$68") (pinfunction "ID_SC*_P$68") (pintype "bidirectional"))
      (node (ref "STM32F303VB") (pin "92") (pinfunction "PB6_92") (pintype "bidirectional"))
      (node (ref "U1") (pin "36") (pinfunction "IO22_36") (pintype "bidirectional"))
    )
    (net (code "74") (name "/SDA") (class "Default")
      (node (ref "EXPANSION_MODULE") (pin "20") (pinfunction "20_20") (pintype "passive"))
      (node (ref "PCB2") (pin "P$67") (pinfunction "ID_SD*_P$67") (pintype "bidirectional"))
      (node (ref "STM32F303VB") (pin "93") (pinfunction "PB7_93") (pintype "bidirectional"))
      (node (ref "U1") (pin "33") (pinfunction "IO21_33") (pintype "bidirectional"))
    )
    (net (code "75") (name "/SPI3_CLK") (class "Default")
      (node (ref "SJ15") (pin "1") (pinfunction "1_1") (pintype "passive"))
      (node (ref "STM32F303VB") (pin "78") (pinfunction "PC10_78") (pintype "bidirectional"))
    )
    (net (code "76") (name "/SPI3_CS") (class "Default")
      (node (ref "SJ14") (pin "2") (pinfunction "2_2") (pintype "passive"))
      (node (ref "STM32F303VB") (pin "77") (pinfunction "PA15_77") (pintype "bidirectional"))
    )
    (net (code "77") (name "/SPI3_CS_ESP") (class "Default")
      (node (ref "STM32F303VB") (pin "84") (pinfunction "PD3_84") (pintype "bidirectional"))
    )
    (net (code "78") (name "/SPI3_MISO") (class "Default")
      (node (ref "SJ16") (pin "1") (pinfunction "1_1") (pintype "passive"))
      (node (ref "STM32F303VB") (pin "79") (pinfunction "PC11_79") (pintype "bidirectional"))
    )
    (net (code "79") (name "/SPI3_MOSI") (class "Default")
      (node (ref "SJ17") (pin "1") (pinfunction "1_1") (pintype "passive"))
      (node (ref "STM32F303VB") (pin "80") (pinfunction "PC12_80") (pintype "bidirectional"))
    )
    (net (code "80") (name "/SPI_CLK") (class "Default")
      (node (ref "RFM69HCW") (pin "13") (pinfunction "SCK_13") (pintype "input"))
      (node (ref "SJ10") (pin "2") (pinfunction "2_2") (pintype "passive"))
      (node (ref "SJ15") (pin "2") (pinfunction "2_2") (pintype "passive"))
      (node (ref "SJ7") (pin "1") (pinfunction "1_1") (pintype "passive"))
    )
    (net (code "81") (name "/SWCLK") (class "Default")
      (node (ref "JP3") (pin "7") (pinfunction "7_7") (pintype "passive"))
      (node (ref "STM32F303VB") (pin "76") (pinfunction "PA14_76") (pintype "bidirectional"))
    )
    (net (code "82") (name "/SWDIO") (class "Default")
      (node (ref "JP3") (pin "8") (pinfunction "8_8") (pintype "passive"))
      (node (ref "STM32F303VB") (pin "72") (pinfunction "PA13_72") (pintype "bidirectional"))
    )
    (net (code "83") (name "/UART1_RX") (class "Default")
      (node (ref "PCB2") (pin "P$48") (pinfunction "GPIO14_P$48") (pintype "bidirectional"))
      (node (ref "SJ11") (pin "1") (pinfunction "1_1") (pintype "passive"))
      (node (ref "SJ20") (pin "1") (pinfunction "1_1") (pintype "passive"))
    )
    (net (code "84") (name "/UART1_TX") (class "Default")
      (node (ref "PCB2") (pin "P$50") (pinfunction "GPIO15_P$50") (pintype "bidirectional"))
      (node (ref "SJ12") (pin "1") (pinfunction "1_1") (pintype "passive"))
      (node (ref "SJ21") (pin "1") (pinfunction "1_1") (pintype "passive"))
    )
    (net (code "85") (name "/UART2_RX") (class "Default")
      (node (ref "JP3") (pin "4") (pinfunction "4_4") (pintype "passive"))
      (node (ref "STM32F303VB") (pin "26") (pinfunction "PA3_26") (pintype "bidirectional"))
    )
    (net (code "86") (name "/UART2_TX") (class "Default")
      (node (ref "JP3") (pin "5") (pinfunction "5_5") (pintype "passive"))
      (node (ref "STM32F303VB") (pin "25") (pinfunction "PA2_25") (pintype "bidirectional"))
      (node (ref "STM32F303VB") (pin "86") (pinfunction "PD5_86") (pintype "bidirectional"))
    )
    (net (code "87") (name "/USART3_RX") (class "Default")
      (node (ref "SJ3") (pin "2") (pinfunction "2_2") (pintype "passive"))
      (node (ref "STM32F303VB") (pin "48") (pinfunction "PB11_48") (pintype "bidirectional"))
    )
    (net (code "88") (name "/USART3_TX") (class "Default")
      (node (ref "SJ18") (pin "2") (pinfunction "2_2") (pintype "passive"))
      (node (ref "STM32F303VB") (pin "47") (pinfunction "PB10_47") (pintype "bidirectional"))
    )
    (net (code "89") (name "/VBAT") (class "Default")
      (node (ref "C23") (pin "+") (pinfunction "+_+") (pintype "passive"))
      (node (ref "Q4") (pin "2") (pinfunction "S_2") (pintype "passive"))
      (node (ref "STM32F303VB") (pin "6") (pinfunction "VBAT_6") (pintype "bidirectional"))
    )
    (net (code "90") (name "/VSIG1") (class "Default")
      (node (ref "CFV1") (pin "2") (pinfunction "2_2") (pintype "passive"))
      (node (ref "D2") (pin "K") (pinfunction "C_K") (pintype "passive"))
      (node (ref "RFV1") (pin "2") (pinfunction "2_2") (pintype "passive"))
      (node (ref "STM32F303VB") (pin "23") (pinfunction "PA0_23") (pintype "bidirectional"))
    )
    (net (code "91") (name "/VSIG2") (class "Default")
      (node (ref "CFV2") (pin "2") (pinfunction "2_2") (pintype "passive"))
      (node (ref "D3") (pin "K") (pinfunction "C_K") (pintype "passive"))
      (node (ref "RFV2") (pin "2") (pinfunction "2_2") (pintype "passive"))
      (node (ref "STM32F303VB") (pin "24") (pinfunction "PA1_24") (pintype "bidirectional"))
    )
    (net (code "92") (name "/VSIG3") (class "Default")
      (node (ref "CFV3") (pin "2") (pinfunction "2_2") (pintype "passive"))
      (node (ref "D4") (pin "K") (pinfunction "C_K") (pintype "passive"))
      (node (ref "RFV3") (pin "2") (pinfunction "2_2") (pintype "passive"))
      (node (ref "STM32F303VB") (pin "27") (pinfunction "PF4_27") (pintype "bidirectional"))
    )
    (net (code "93") (name "/VSIG4") (class "Default")
      (node (ref "STM32F303VB") (pin "17") (pinfunction "PC2_17") (pintype "bidirectional"))
    )
    (net (code "94") (name "/VSIG5") (class "Default")
      (node (ref "STM32F303VB") (pin "18") (pinfunction "PC3_18") (pintype "bidirectional"))
    )
    (net (code "95") (name "/VSIG6") (class "Default")
      (node (ref "STM32F303VB") (pin "19") (pinfunction "PF2_19") (pintype "bidirectional"))
    )
    (net (code "96") (name "/VT1_EX") (class "Default")
      (node (ref "EXPANSION_MODULE") (pin "11") (pinfunction "11_11") (pintype "passive"))
    )
    (net (code "97") (name "/VT2_EX") (class "Default")
      (node (ref "EXPANSION_MODULE") (pin "12") (pinfunction "12_12") (pintype "passive"))
    )
    (net (code "98") (name "/VT3_EX") (class "Default")
      (node (ref "EXPANSION_MODULE") (pin "13") (pinfunction "13_13") (pintype "passive"))
    )
    (net (code "99") (name "GND") (class "Default")
      (node (ref "3POLE_1") (pin "P$3") (pinfunction "3_P$3") (pintype "bidirectional"))
      (node (ref "3POLE_2") (pin "P$3") (pinfunction "3_P$3") (pintype "bidirectional"))
      (node (ref "3POLE_3") (pin "P$3") (pinfunction "3_P$3") (pintype "bidirectional"))
      (node (ref "3POLE_4") (pin "P$3") (pinfunction "3_P$3") (pintype "bidirectional"))
      (node (ref "3POLE_5") (pin "P$3") (pinfunction "3_P$3") (pintype "bidirectional"))
      (node (ref "3POLE_6") (pin "P$3") (pinfunction "3_P$3") (pintype "bidirectional"))
      (node (ref "3POLE_7") (pin "P$1") (pinfunction "1_P$1") (pintype "bidirectional"))
      (node (ref "BOOT_ESP") (pin "1") (pinfunction "1_1") (pintype "passive"))
      (node (ref "C10") (pin "2") (pinfunction "2_2") (pintype "passive"))
      (node (ref "C11") (pin "2") (pinfunction "2_2") (pintype "passive"))
      (node (ref "C12") (pin "2") (pinfunction "2_2") (pintype "passive"))
      (node (ref "C13") (pin "2") (pinfunction "2_2") (pintype "passive"))
      (node (ref "C14") (pin "2") (pinfunction "2_2") (pintype "passive"))
      (node (ref "C15") (pin "2") (pinfunction "2_2") (pintype "passive"))
      (node (ref "C17") (pin "2") (pinfunction "2_2") (pintype "passive"))
      (node (ref "C18") (pin "2") (pinfunction "2_2") (pintype "passive"))
      (node (ref "C19") (pin "2") (pinfunction "2_2") (pintype "passive"))
      (node (ref "C2") (pin "2") (pinfunction "2_2") (pintype "passive"))
      (node (ref "C20") (pin "2") (pinfunction "2_2") (pintype "passive"))
      (node (ref "C21") (pin "2") (pinfunction "2_2") (pintype "passive"))
      (node (ref "C22") (pin "2") (pinfunction "2_2") (pintype "passive"))
      (node (ref "C23") (pin "-") (pinfunction "-_-") (pintype "passive"))
      (node (ref "C24") (pin "2") (pinfunction "2_2") (pintype "passive"))
      (node (ref "C25") (pin "2") (pinfunction "2_2") (pintype "passive"))
      (node (ref "C26") (pin "2") (pinfunction "2_2") (pintype "passive"))
      (node (ref "C27") (pin "2") (pinfunction "2_2") (pintype "passive"))
      (node (ref "C28") (pin "2") (pinfunction "2_2") (pintype "passive"))
      (node (ref "C29") (pin "2") (pinfunction "2_2") (pintype "passive"))
      (node (ref "C3") (pin "1") (pinfunction "1_1") (pintype "passive"))
      (node (ref "C30") (pin "2") (pinfunction "2_2") (pintype "passive"))
      (node (ref "C4") (pin "1") (pinfunction "1_1") (pintype "passive"))
      (node (ref "C5") (pin "1") (pinfunction "1_1") (pintype "passive"))
      (node (ref "C50*") (pin "1") (pinfunction "1_1") (pintype "passive"))
      (node (ref "C6") (pin "1") (pinfunction "1_1") (pintype "passive"))
      (node (ref "C7") (pin "2") (pinfunction "2_2") (pintype "passive"))
      (node (ref "C8") (pin "1") (pinfunction "1_1") (pintype "passive"))
      (node (ref "C9") (pin "1") (pinfunction "1_1") (pintype "passive"))
      (node (ref "CF1") (pin "1") (pinfunction "1_1") (pintype "passive"))
      (node (ref "CF2") (pin "1") (pinfunction "1_1") (pintype "passive"))
      (node (ref "CF3") (pin "1") (pinfunction "1_1") (pintype "passive"))
      (node (ref "CF4") (pin "1") (pinfunction "1_1") (pintype "passive"))
      (node (ref "CF5") (pin "1") (pinfunction "1_1") (pintype "passive"))
      (node (ref "CF6") (pin "1") (pinfunction "1_1") (pintype "passive"))
      (node (ref "CF7") (pin "1") (pinfunction "1_1") (pintype "passive"))
      (node (ref "CF8") (pin "1") (pinfunction "1_1") (pintype "passive"))
      (node (ref "CF9") (pin "1") (pinfunction "1_1") (pintype "passive"))
      (node (ref "CFV1") (pin "1") (pinfunction "1_1") (pintype "passive"))
      (node (ref "CFV2") (pin "1") (pinfunction "1_1") (pintype "passive"))
      (node (ref "CFV3") (pin "1") (pinfunction "1_1") (pintype "passive"))
      (node (ref "D1") (pin "A") (pinfunction "A_A") (pintype "passive"))
      (node (ref "D10") (pin "A") (pinfunction "A_A") (pintype "passive"))
      (node (ref "D11") (pin "A") (pinfunction "A_A") (pintype "passive"))
      (node (ref "D12") (pin "A") (pinfunction "A_A") (pintype "passive"))
      (node (ref "D13") (pin "A") (pinfunction "A_A") (pintype "passive"))
      (node (ref "D14") (pin "A") (pinfunction "A_A") (pintype "passive"))
      (node (ref "D15") (pin "A") (pinfunction "A_A") (pintype "passive"))
      (node (ref "D16") (pin "A") (pinfunction "A_A") (pintype "passive"))
      (node (ref "D17") (pin "A") (pinfunction "A_A") (pintype "passive"))
      (node (ref "D18") (pin "A") (pinfunction "A_A") (pintype "passive"))
      (node (ref "D19") (pin "A") (pinfunction "A_A") (pintype "passive"))
      (node (ref "D2") (pin "A") (pinfunction "A_A") (pintype "passive"))
      (node (ref "D22") (pin "A") (pinfunction "A_A") (pintype "passive"))
      (node (ref "D23") (pin "A") (pinfunction "A_A") (pintype "passive"))
      (node (ref "D25") (pin "A") (pinfunction "A_A") (pintype "passive"))
      (node (ref "D3") (pin "A") (pinfunction "A_A") (pintype "passive"))
      (node (ref "D4") (pin "A") (pinfunction "A_A") (pintype "passive"))
      (node (ref "D41*") (pin "A") (pinfunction "A_A") (pintype "passive"))
      (node (ref "D5") (pin "A") (pinfunction "A_A") (pintype "passive"))
      (node (ref "D6") (pin "A") (pinfunction "A_A") (pintype "passive"))
      (node (ref "D7") (pin "A") (pinfunction "A_A") (pintype "passive"))
      (node (ref "D8") (pin "A") (pinfunction "A_A") (pintype "passive"))
      (node (ref "D9") (pin "A") (pinfunction "A_A") (pintype "passive"))
      (node (ref "EXPANSION_MODULE") (pin "1") (pinfunction "1_1") (pintype "passive"))
      (node (ref "EXPANSION_MODULE") (pin "14") (pinfunction "14_14") (pintype "passive"))
      (node (ref "EXPANSION_MODULE") (pin "26") (pinfunction "26_26") (pintype "passive"))
      (node (ref "J$1") (pin "GND@0") (pinfunction "GND_GND@0") (pintype "bidirectional"))
      (node (ref "J$1") (pin "GND@1") (pinfunction "GND_GND@1") (pintype "bidirectional"))
      (node (ref "J$1") (pin "GND@2") (pinfunction "GND_GND@2") (pintype "bidirectional"))
      (node (ref "J$1") (pin "GND@3") (pinfunction "GND_GND@3") (pintype "bidirectional"))
      (node (ref "JP1") (pin "1") (pinfunction "1_1") (pintype "passive"))
      (node (ref "JP3") (pin "1") (pinfunction "1_1") (pintype "passive"))
      (node (ref "LED1") (pin "C") (pinfunction "C_C") (pintype "passive"))
      (node (ref "LED2") (pin "C") (pinfunction "C_C") (pintype "passive"))
      (node (ref "LED3") (pin "C") (pinfunction "C_C") (pintype "passive"))
      (node (ref "LED4") (pin "C") (pinfunction "C_C") (pintype "passive"))
      (node (ref "MCP1825") (pin "2") (pinfunction "GND_2") (pintype "power_in"))
      (node (ref "MCP1825") (pin "4") (pinfunction "GND_4") (pintype "power_in"))
      (node (ref "PCB2") (pin "P$46") (pinfunction "GND_P$46") (pintype "bidirectional"))
      (node (ref "PCB2") (pin "P$49") (pinfunction "GND_P$49") (pintype "bidirectional"))
      (node (ref "PCB2") (pin "P$54") (pinfunction "GND_P$54") (pintype "bidirectional"))
      (node (ref "PCB2") (pin "P$60") (pinfunction "GND_P$60") (pintype "bidirectional"))
      (node (ref "PCB2") (pin "P$65") (pinfunction "GND_P$65") (pintype "bidirectional"))
      (node (ref "PCB2") (pin "P$70") (pinfunction "GND_P$70") (pintype "bidirectional"))
      (node (ref "PCB2") (pin "P$74") (pinfunction "GND_P$74") (pintype "bidirectional"))
      (node (ref "PCB2") (pin "P$79") (pinfunction "GND_P$79") (pintype "bidirectional"))
      (node (ref "Q2") (pin "2") (pinfunction "E_2") (pintype "passive"))
      (node (ref "Q3") (pin "2") (pinfunction "E_2") (pintype "passive"))
      (node (ref "Q4") (pin "1") (pinfunction "G_1") (pintype "passive"))
      (node (ref "R14") (pin "1") (pinfunction "1_1") (pintype "passive"))
      (node (ref "R15") (pin "1") (pinfunction "1_1") (pintype "passive"))
      (node (ref "R16") (pin "1") (pinfunction "1_1") (pintype "passive"))
      (node (ref "R2") (pin "2") (pinfunction "2_2") (pintype "passive"))
      (node (ref "R23") (pin "1") (pinfunction "1_1") (pintype "passive"))
      (node (ref "RFM69HCW") (pin "10") (pinfunction "GND_10") (pintype "passive"))
      (node (ref "RFM69HCW") (pin "7") (pinfunction "GND_7") (pintype "passive"))
      (node (ref "RJ45_1") (pin "1") (pinfunction "1_1") (pintype "bidirectional"))
      (node (ref "RJ45_1") (pin "3") (pinfunction "3_3") (pintype "bidirectional"))
      (node (ref "RJ45_1") (pin "5") (pinfunction "5_5") (pintype "bidirectional"))
      (node (ref "S1") (pin "1") (pinfunction "1_1") (pintype "bidirectional"))
      (node (ref "S2") (pin "1") (pinfunction "1_1") (pintype "bidirectional"))
      (node (ref "STM32F303VB") (pin "20") (pinfunction "VSSA/VREF-_20") (pintype "bidirectional"))
      (node (ref "STM32F303VB") (pin "49") (pinfunction "VSS_49") (pintype "bidirectional"))
      (node (ref "STM32F303VB") (pin "74") (pinfunction "VSS_74") (pintype "bidirectional"))
      (node (ref "STM32F303VB") (pin "99") (pinfunction "VSS_99") (pintype "bidirectional"))
      (node (ref "U$2") (pin "P$1") (pinfunction "GND_P$1") (pintype "bidirectional"))
      (node (ref "U$2") (pin "P$2") (pinfunction "GND._P$2") (pintype "bidirectional"))
      (node (ref "U1") (pin "1") (pinfunction "GND_1") (pintype "power_in"))
      (node (ref "U1") (pin "15") (pinfunction "GND_15") (pintype "power_in"))
      (node (ref "U1") (pin "38") (pinfunction "GND_38") (pintype "power_in"))
      (node (ref "U1") (pin "39") (pinfunction "GND_39") (pintype "power_in"))
      (node (ref "USB-C") (pin "A1") (pinfunction "GND1_A1") (pintype "passive"))
      (node (ref "USB-C") (pin "A12") (pinfunction "GND2_A12") (pintype "passive"))
      (node (ref "USB-C") (pin "B1") (pinfunction "GND3_B1") (pintype "passive"))
      (node (ref "USB-C") (pin "B12") (pinfunction "GND4_B12") (pintype "passive"))
      (node (ref "USB-C") (pin "S1") (pinfunction "SHIELD_S1") (pintype "passive"))
      (node (ref "USB-C") (pin "S2") (pinfunction "SHIELD_S2") (pintype "passive"))
      (node (ref "USB-C") (pin "S3") (pinfunction "SHIELD_S3") (pintype "passive"))
      (node (ref "USB-C") (pin "S4") (pinfunction "SHIELD_S4") (pintype "passive"))
      (node (ref "VREF_3V3") (pin "2") (pinfunction "GND_2") (pintype "bidirectional"))
      (node (ref "VREF_3V3") (pin "3") (pinfunction "GND_3") (pintype "bidirectional"))
      (node (ref "VREF_3V3") (pin "5") (pinfunction "GND_5") (pintype "bidirectional"))
    )
    (net (code "100") (name "Net-(C16-Pad1)") (class "Default")
      (node (ref "C16") (pin "1") (pinfunction "1_1") (pintype "passive"))
      (node (ref "JP1") (pin "6") (pinfunction "6_6") (pintype "passive"))
    )
    (net (code "101") (name "Net-(CT1-2)") (class "Default")
      (node (ref "CT1") (pin "P$2") (pinfunction "2_P$2") (pintype "bidirectional"))
      (node (ref "D13") (pin "K") (pinfunction "C_K") (pintype "passive"))
      (node (ref "RB18") (pin "1") (pinfunction "1_1") (pintype "passive"))
      (node (ref "RB9") (pin "1") (pinfunction "1_1") (pintype "passive"))
      (node (ref "RF9") (pin "1") (pinfunction "1_1") (pintype "passive"))
    )
    (net (code "102") (name "Net-(CT2-2)") (class "Default")
      (node (ref "CT2") (pin "P$2") (pinfunction "2_P$2") (pintype "bidirectional"))
      (node (ref "D12") (pin "K") (pinfunction "C_K") (pintype "passive"))
      (node (ref "RB17") (pin "1") (pinfunction "1_1") (pintype "passive"))
      (node (ref "RB8") (pin "1") (pinfunction "1_1") (pintype "passive"))
      (node (ref "RF8") (pin "1") (pinfunction "1_1") (pintype "passive"))
    )
    (net (code "103") (name "Net-(CT3-2)") (class "Default")
      (node (ref "CT3") (pin "P$2") (pinfunction "2_P$2") (pintype "bidirectional"))
      (node (ref "D11") (pin "K") (pinfunction "C_K") (pintype "passive"))
      (node (ref "RB16") (pin "1") (pinfunction "1_1") (pintype "passive"))
      (node (ref "RB7") (pin "1") (pinfunction "1_1") (pintype "passive"))
      (node (ref "RF7") (pin "1") (pinfunction "1_1") (pintype "passive"))
    )
    (net (code "104") (name "Net-(CT4-2)") (class "Default")
      (node (ref "CT4") (pin "P$2") (pinfunction "2_P$2") (pintype "bidirectional"))
      (node (ref "D10") (pin "K") (pinfunction "C_K") (pintype "passive"))
      (node (ref "RB13") (pin "1") (pinfunction "1_1") (pintype "passive"))
      (node (ref "RB6") (pin "1") (pinfunction "1_1") (pintype "passive"))
      (node (ref "RF6") (pin "1") (pinfunction "1_1") (pintype "passive"))
    )
    (net (code "105") (name "Net-(CT5-2)") (class "Default")
      (node (ref "CT5") (pin "P$2") (pinfunction "2_P$2") (pintype "bidirectional"))
      (node (ref "D9") (pin "K") (pinfunction "C_K") (pintype "passive"))
      (node (ref "RB14") (pin "1") (pinfunction "1_1") (pintype "passive"))
      (node (ref "RB5") (pin "1") (pinfunction "1_1") (pintype "passive"))
      (node (ref "RF5") (pin "1") (pinfunction "1_1") (pintype "passive"))
    )
    (net (code "106") (name "Net-(CT6-2)") (class "Default")
      (node (ref "CT6") (pin "P$2") (pinfunction "2_P$2") (pintype "bidirectional"))
      (node (ref "D8") (pin "K") (pinfunction "C_K") (pintype "passive"))
      (node (ref "RB15") (pin "1") (pinfunction "1_1") (pintype "passive"))
      (node (ref "RB4") (pin "1") (pinfunction "1_1") (pintype "passive"))
      (node (ref "RF4") (pin "1") (pinfunction "1_1") (pintype "passive"))
    )
    (net (code "107") (name "Net-(CT7-2)") (class "Default")
      (node (ref "CT7") (pin "P$2") (pinfunction "2_P$2") (pintype "bidirectional"))
      (node (ref "D7") (pin "K") (pinfunction "C_K") (pintype "passive"))
      (node (ref "RB12") (pin "1") (pinfunction "1_1") (pintype "passive"))
      (node (ref "RB3") (pin "1") (pinfunction "1_1") (pintype "passive"))
      (node (ref "RF3") (pin "1") (pinfunction "1_1") (pintype "passive"))
    )
    (net (code "108") (name "Net-(CT8-2)") (class "Default")
      (node (ref "CT8") (pin "P$2") (pinfunction "2_P$2") (pintype "bidirectional"))
      (node (ref "D6") (pin "K") (pinfunction "C_K") (pintype "passive"))
      (node (ref "RB11") (pin "1") (pinfunction "1_1") (pintype "passive"))
      (node (ref "RB2") (pin "1") (pinfunction "1_1") (pintype "passive"))
      (node (ref "RF2") (pin "1") (pinfunction "1_1") (pintype "passive"))
    )
    (net (code "109") (name "Net-(CT9-2)") (class "Default")
      (node (ref "CT9") (pin "P$2") (pinfunction "2_P$2") (pintype "bidirectional"))
      (node (ref "D5") (pin "K") (pinfunction "C_K") (pintype "passive"))
      (node (ref "RB1") (pin "1") (pinfunction "1_1") (pintype "passive"))
      (node (ref "RB10") (pin "1") (pinfunction "1_1") (pintype "passive"))
      (node (ref "RF1") (pin "1") (pinfunction "1_1") (pintype "passive"))
    )
    (net (code "110") (name "Net-(D25-C)") (class "Default")
      (node (ref "D24") (pin "A") (pinfunction "A_A") (pintype "passive"))
      (node (ref "D25") (pin "K") (pinfunction "C_K") (pintype "passive"))
    )
    (net (code "111") (name "Net-(D41*-C)") (class "Default")
      (node (ref "D40*") (pin "A") (pinfunction "A_A") (pintype "passive"))
      (node (ref "D41*") (pin "K") (pinfunction "C_K") (pintype "passive"))
    )
    (net (code "112") (name "Net-(J$1-SIGNAL)") (class "Default")
      (node (ref "J$1") (pin "SIG") (pinfunction "SIGNAL_SIG") (pintype "bidirectional"))
      (node (ref "RFM69HCW") (pin "8") (pinfunction "ANT_8") (pintype "bidirectional"))
    )
    (net (code "113") (name "Net-(JP3-Pad2)") (class "Default")
      (node (ref "JP3") (pin "2") (pinfunction "2_2") (pintype "passive"))
      (node (ref "SJ1") (pin "1") (pinfunction "1_1") (pintype "passive"))
    )
    (net (code "114") (name "Net-(LED1-PadA)") (class "Default")
      (node (ref "LED1") (pin "A") (pinfunction "A_A") (pintype "passive"))
      (node (ref "R3") (pin "1") (pinfunction "1_1") (pintype "passive"))
    )
    (net (code "115") (name "Net-(LED2-PadA)") (class "Default")
      (node (ref "LED2") (pin "A") (pinfunction "A_A") (pintype "passive"))
      (node (ref "R4") (pin "1") (pinfunction "1_1") (pintype "passive"))
    )
    (net (code "116") (name "Net-(LED3-PadA)") (class "Default")
      (node (ref "LED3") (pin "A") (pinfunction "A_A") (pintype "passive"))
      (node (ref "R5") (pin "1") (pinfunction "1_1") (pintype "passive"))
    )
    (net (code "117") (name "Net-(LED4-PadA)") (class "Default")
      (node (ref "LED4") (pin "A") (pinfunction "A_A") (pintype "passive"))
      (node (ref "R10") (pin "1") (pinfunction "1_1") (pintype "passive"))
    )
    (net (code "118") (name "Net-(PCB2-GPIO12)") (class "Default")
      (node (ref "PCB2") (pin "P$72") (pinfunction "GPIO12_P$72") (pintype "bidirectional"))
      (node (ref "SJ8") (pin "1") (pinfunction "1_1") (pintype "passive"))
    )
    (net (code "119") (name "Net-(Q1-B)") (class "Default")
      (node (ref "Q1") (pin "1") (pinfunction "B_1") (pintype "passive"))
      (node (ref "Q3") (pin "3") (pinfunction "C_3") (pintype "passive"))
      (node (ref "R14") (pin "2") (pinfunction "2_2") (pintype "passive"))
      (node (ref "R9") (pin "1") (pinfunction "1_1") (pintype "passive"))
    )
    (net (code "120") (name "Net-(Q1-C)") (class "Default")
      (node (ref "Q1") (pin "3") (pinfunction "C_3") (pintype "passive"))
      (node (ref "Q2") (pin "1") (pinfunction "B_1") (pintype "passive"))
      (node (ref "R16") (pin "2") (pinfunction "2_2") (pintype "passive"))
    )
    (net (code "121") (name "Net-(Q2-C)") (class "Default")
      (node (ref "Q2") (pin "3") (pinfunction "C_3") (pintype "passive"))
      (node (ref "R11") (pin "1") (pinfunction "1_1") (pintype "passive"))
      (node (ref "R15") (pin "2") (pinfunction "2_2") (pintype "passive"))
      (node (ref "R19") (pin "1") (pinfunction "1_1") (pintype "passive"))
    )
    (net (code "122") (name "Net-(Q3-B)") (class "Default")
      (node (ref "Q3") (pin "1") (pinfunction "B_1") (pintype "passive"))
      (node (ref "R18") (pin "1") (pinfunction "1_1") (pintype "passive"))
    )
    (net (code "123") (name "Net-(RB16-Pad2)") (class "Default")
      (node (ref "RB16") (pin "2") (pinfunction "2_2") (pintype "passive"))
      (node (ref "RB7") (pin "2") (pinfunction "2_2") (pintype "passive"))
      (node (ref "S33") (pin "1") (pinfunction "1_1") (pintype "passive"))
    )
    (net (code "124") (name "Net-(RB17-Pad2)") (class "Default")
      (node (ref "RB17") (pin "2") (pinfunction "2_2") (pintype "passive"))
      (node (ref "RB8") (pin "2") (pinfunction "2_2") (pintype "passive"))
      (node (ref "S22") (pin "1") (pinfunction "1_1") (pintype "passive"))
    )
    (net (code "125") (name "Net-(RB18-Pad2)") (class "Default")
      (node (ref "RB18") (pin "2") (pinfunction "2_2") (pintype "passive"))
      (node (ref "RB9") (pin "2") (pinfunction "2_2") (pintype "passive"))
      (node (ref "S11") (pin "1") (pinfunction "1_1") (pintype "passive"))
    )
    (net (code "126") (name "Net-(RFV1-Pad1)") (class "Default")
      (node (ref "RFV1") (pin "1") (pinfunction "1_1") (pintype "passive"))
      (node (ref "RVPU1") (pin "1") (pinfunction "1_1") (pintype "passive"))
      (node (ref "RVPU11") (pin "1") (pinfunction "1_1") (pintype "passive"))
    )
    (net (code "127") (name "Net-(RFV2-Pad1)") (class "Default")
      (node (ref "RFV2") (pin "1") (pinfunction "1_1") (pintype "passive"))
      (node (ref "RVPU2") (pin "1") (pinfunction "1_1") (pintype "passive"))
      (node (ref "RVPU22") (pin "1") (pinfunction "1_1") (pintype "passive"))
    )
    (net (code "128") (name "Net-(RFV3-Pad1)") (class "Default")
      (node (ref "RFV3") (pin "1") (pinfunction "1_1") (pintype "passive"))
      (node (ref "RVPU3") (pin "2") (pinfunction "2_2") (pintype "passive"))
      (node (ref "RVPU33") (pin "1") (pinfunction "1_1") (pintype "passive"))
    )
    (net (code "129") (name "Net-(STM32F303VB-PA9)") (class "Default")
      (node (ref "STM32F303VB") (pin "68") (pinfunction "PA9_68") (pintype "bidirectional"))
      (node (ref "UART1") (pin "2") (pinfunction "2_2") (pintype "passive"))
    )
    (net (code "130") (name "Net-(STM32F303VB-PA10)") (class "Default")
      (node (ref "STM32F303VB") (pin "69") (pinfunction "PA10_69") (pintype "bidirectional"))
      (node (ref "UART1") (pin "1") (pinfunction "1_1") (pintype "passive"))
    )
    (net (code "131") (name "Net-(U1-EN)") (class "Default")
      (node (ref "C16") (pin "2") (pinfunction "2_2") (pintype "passive"))
      (node (ref "U1") (pin "3") (pinfunction "EN_3") (pintype "input"))
    )
    (net (code "132") (name "Net-(U1-IO0)") (class "Default")
      (node (ref "BOOT_ESP") (pin "2") (pinfunction "2_2") (pintype "passive"))
      (node (ref "U1") (pin "25") (pinfunction "IO0_25") (pintype "bidirectional"))
    )
    (net (code "133") (name "Net-(U1-RXD0)") (class "Default")
      (node (ref "JP1") (pin "4") (pinfunction "4_4") (pintype "passive"))
      (node (ref "SJ18") (pin "1") (pinfunction "1_1") (pintype "passive"))
      (node (ref "SJ21") (pin "2") (pinfunction "2_2") (pintype "passive"))
      (node (ref "U1") (pin "34") (pinfunction "RXD0_34") (pintype "bidirectional"))
    )
    (net (code "134") (name "Net-(U1-TXD0)") (class "Default")
      (node (ref "JP1") (pin "5") (pinfunction "5_5") (pintype "passive"))
      (node (ref "SJ20") (pin "2") (pinfunction "2_2") (pintype "passive"))
      (node (ref "SJ3") (pin "1") (pinfunction "1_1") (pintype "passive"))
      (node (ref "U1") (pin "35") (pinfunction "TXD0_35") (pintype "bidirectional"))
    )
    (net (code "135") (name "Net-(VT1-TIP)") (class "Default")
      (node (ref "RVPU1") (pin "2") (pinfunction "2_2") (pintype "passive"))
      (node (ref "VT1") (pin "PWR2") (pinfunction "TIP_PWR2") (pintype "bidirectional"))
    )
    (net (code "136") (name "Net-(VT2-TIP)") (class "Default")
      (node (ref "RVPU2") (pin "2") (pinfunction "2_2") (pintype "passive"))
      (node (ref "VT2") (pin "PWR2") (pinfunction "TIP_PWR2") (pintype "bidirectional"))
    )
    (net (code "137") (name "Net-(VT3-TIP)") (class "Default")
      (node (ref "RVPU3") (pin "1") (pinfunction "1_1") (pintype "passive"))
      (node (ref "VT3") (pin "PWR2") (pinfunction "TIP_PWR2") (pintype "bidirectional"))
    )
    (net (code "138") (name "unconnected-(CT1-3-PadP$3)") (class "Default")
      (node (ref "CT1") (pin "P$3") (pinfunction "3_P$3") (pintype "bidirectional"))
    )
    (net (code "139") (name "unconnected-(CT2-3-PadP$3)") (class "Default")
      (node (ref "CT2") (pin "P$3") (pinfunction "3_P$3") (pintype "bidirectional"))
    )
    (net (code "140") (name "unconnected-(CT3-3-PadP$3)") (class "Default")
      (node (ref "CT3") (pin "P$3") (pinfunction "3_P$3") (pintype "bidirectional"))
    )
    (net (code "141") (name "unconnected-(CT4-3-PadP$3)") (class "Default")
      (node (ref "CT4") (pin "P$3") (pinfunction "3_P$3") (pintype "bidirectional"))
    )
    (net (code "142") (name "unconnected-(CT5-3-PadP$3)") (class "Default")
      (node (ref "CT5") (pin "P$3") (pinfunction "3_P$3") (pintype "bidirectional"))
    )
    (net (code "143") (name "unconnected-(CT6-3-PadP$3)") (class "Default")
      (node (ref "CT6") (pin "P$3") (pinfunction "3_P$3") (pintype "bidirectional"))
    )
    (net (code "144") (name "unconnected-(CT7-3-PadP$3)") (class "Default")
      (node (ref "CT7") (pin "P$3") (pinfunction "3_P$3") (pintype "bidirectional"))
    )
    (net (code "145") (name "unconnected-(CT8-3-PadP$3)") (class "Default")
      (node (ref "CT8") (pin "P$3") (pinfunction "3_P$3") (pintype "bidirectional"))
    )
    (net (code "146") (name "unconnected-(CT9-3-PadP$3)") (class "Default")
      (node (ref "CT9") (pin "P$3") (pinfunction "3_P$3") (pintype "bidirectional"))
    )
    (net (code "147") (name "unconnected-(PCB2-3V3-PadP$41)") (class "Default")
      (node (ref "PCB2") (pin "P$41") (pinfunction "3V3_P$41") (pintype "bidirectional"))
    )
    (net (code "148") (name "unconnected-(PCB2-3V3-PadP$57)") (class "Default")
      (node (ref "PCB2") (pin "P$57") (pinfunction "3V3_P$57") (pintype "bidirectional"))
    )
    (net (code "149") (name "unconnected-(PCB2-GPIO2-PadP$43)") (class "Default")
      (node (ref "PCB2") (pin "P$43") (pinfunction "GPIO2_P$43") (pintype "bidirectional"))
    )
    (net (code "150") (name "unconnected-(PCB2-GPIO3-PadP$45)") (class "Default")
      (node (ref "PCB2") (pin "P$45") (pinfunction "GPIO3_P$45") (pintype "bidirectional"))
    )
    (net (code "151") (name "unconnected-(PCB2-GPIO6-PadP$71)") (class "Default")
      (node (ref "PCB2") (pin "P$71") (pinfunction "GPIO6_P$71") (pintype "bidirectional"))
    )
    (net (code "152") (name "unconnected-(PCB2-GPIO7-PadP$66)") (class "Default")
      (node (ref "PCB2") (pin "P$66") (pinfunction "GPIO7_P$66") (pintype "bidirectional"))
    )
    (net (code "153") (name "unconnected-(PCB2-GPIO13-PadP$73)") (class "Default")
      (node (ref "PCB2") (pin "P$73") (pinfunction "GPIO13_P$73") (pintype "bidirectional"))
    )
    (net (code "154") (name "unconnected-(PCB2-GPIO17-PadP$51)") (class "Default")
      (node (ref "PCB2") (pin "P$51") (pinfunction "GPIO17_P$51") (pintype "bidirectional"))
    )
    (net (code "155") (name "unconnected-(PCB2-GPIO19-PadP$75)") (class "Default")
      (node (ref "PCB2") (pin "P$75") (pinfunction "GPIO19_P$75") (pintype "bidirectional"))
    )
    (net (code "156") (name "unconnected-(PCB2-GPIO21-PadP$80)") (class "Default")
      (node (ref "PCB2") (pin "P$80") (pinfunction "GPIO21_P$80") (pintype "bidirectional"))
    )
    (net (code "157") (name "unconnected-(PCB2-GPIO22-PadP$55)") (class "Default")
      (node (ref "PCB2") (pin "P$55") (pinfunction "GPIO22_P$55") (pintype "bidirectional"))
    )
    (net (code "158") (name "unconnected-(PCB2-GPIO25-PadP$62)") (class "Default")
      (node (ref "PCB2") (pin "P$62") (pinfunction "GPIO25_P$62") (pintype "bidirectional"))
    )
    (net (code "159") (name "unconnected-(PCB2-GPIO26-PadP$77)") (class "Default")
      (node (ref "PCB2") (pin "P$77") (pinfunction "GPIO26_P$77") (pintype "bidirectional"))
    )
    (net (code "160") (name "unconnected-(PCB2-GPIO27-PadP$53)") (class "Default")
      (node (ref "PCB2") (pin "P$53") (pinfunction "GPIO27_P$53") (pintype "bidirectional"))
    )
    (net (code "161") (name "unconnected-(RFM69HCW-CLK-Pad5)") (class "Default")
      (node (ref "RFM69HCW") (pin "5") (pinfunction "CLK_5") (pintype "output"))
    )
    (net (code "162") (name "unconnected-(RFM69HCW-DCLK{slash}CFIL{slash}FFIT-Pad4)") (class "Default")
      (node (ref "RFM69HCW") (pin "4") (pinfunction "DCLK/CFIL/FFIT_4") (pintype "bidirectional"))
    )
    (net (code "163") (name "unconnected-(RFM69HCW-FSK{slash}DATA{slash}NFFS-Pad3)") (class "Default")
      (node (ref "RFM69HCW") (pin "3") (pinfunction "FSK/DATA/NFFS_3") (pintype "bidirectional"))
    )
    (net (code "164") (name "unconnected-(RFM69HCW-~{INT}-Pad11)") (class "Default")
      (node (ref "RFM69HCW") (pin "11") (pinfunction "~{INT}_11") (pintype "bidirectional"))
    )
    (net (code "165") (name "unconnected-(STM32F303VB-PB2-Pad37)") (class "Default")
      (node (ref "STM32F303VB") (pin "37") (pinfunction "PB2_37") (pintype "bidirectional"))
    )
    (net (code "166") (name "unconnected-(STM32F303VB-PB4-Pad90)") (class "Default")
      (node (ref "STM32F303VB") (pin "90") (pinfunction "PB4_90") (pintype "bidirectional"))
    )
    (net (code "167") (name "unconnected-(STM32F303VB-PB13-Pad52)") (class "Default")
      (node (ref "STM32F303VB") (pin "52") (pinfunction "PB13_52") (pintype "bidirectional"))
    )
    (net (code "168") (name "unconnected-(STM32F303VB-PC5-Pad34)") (class "Default")
      (node (ref "STM32F303VB") (pin "34") (pinfunction "PC5_34") (pintype "bidirectional"))
    )
    (net (code "169") (name "unconnected-(STM32F303VB-PC13-Pad7)") (class "Default")
      (node (ref "STM32F303VB") (pin "7") (pinfunction "PC13_7") (pintype "bidirectional"))
    )
    (net (code "170") (name "unconnected-(STM32F303VB-PD0-Pad81)") (class "Default")
      (node (ref "STM32F303VB") (pin "81") (pinfunction "PD0_81") (pintype "bidirectional"))
    )
    (net (code "171") (name "unconnected-(STM32F303VB-PD1-Pad82)") (class "Default")
      (node (ref "STM32F303VB") (pin "82") (pinfunction "PD1_82") (pintype "bidirectional"))
    )
    (net (code "172") (name "unconnected-(STM32F303VB-PD2-Pad83)") (class "Default")
      (node (ref "STM32F303VB") (pin "83") (pinfunction "PD2_83") (pintype "bidirectional"))
    )
    (net (code "173") (name "unconnected-(STM32F303VB-PD4-Pad85)") (class "Default")
      (node (ref "STM32F303VB") (pin "85") (pinfunction "PD4_85") (pintype "bidirectional"))
    )
    (net (code "174") (name "unconnected-(STM32F303VB-PD6-Pad87)") (class "Default")
      (node (ref "STM32F303VB") (pin "87") (pinfunction "PD6_87") (pintype "bidirectional"))
    )
    (net (code "175") (name "unconnected-(STM32F303VB-PD7-Pad88)") (class "Default")
      (node (ref "STM32F303VB") (pin "88") (pinfunction "PD7_88") (pintype "bidirectional"))
    )
    (net (code "176") (name "unconnected-(STM32F303VB-PE14-Pad45)") (class "Default")
      (node (ref "STM32F303VB") (pin "45") (pinfunction "PE14_45") (pintype "bidirectional"))
    )
    (net (code "177") (name "unconnected-(STM32F303VB-PE15-Pad46)") (class "Default")
      (node (ref "STM32F303VB") (pin "46") (pinfunction "PE15_46") (pintype "bidirectional"))
    )
    (net (code "178") (name "unconnected-(STM32F303VB-PF6-Pad73)") (class "Default")
      (node (ref "STM32F303VB") (pin "73") (pinfunction "PF6_73") (pintype "bidirectional"))
    )
    (net (code "179") (name "unconnected-(STM32F303VB-PF9-Pad10)") (class "Default")
      (node (ref "STM32F303VB") (pin "10") (pinfunction "PF9_10") (pintype "bidirectional"))
    )
    (net (code "180") (name "unconnected-(STM32F303VB-PF10-Pad11)") (class "Default")
      (node (ref "STM32F303VB") (pin "11") (pinfunction "PF10_11") (pintype "bidirectional"))
    )
    (net (code "181") (name "unconnected-(U1-IO4-Pad26)") (class "Default")
      (node (ref "U1") (pin "26") (pinfunction "IO4_26") (pintype "bidirectional"))
    )
    (net (code "182") (name "unconnected-(U1-IO5-Pad29)") (class "Default")
      (node (ref "U1") (pin "29") (pinfunction "IO5_29") (pintype "bidirectional"))
    )
    (net (code "183") (name "unconnected-(U1-IO17-Pad28)") (class "Default")
      (node (ref "U1") (pin "28") (pinfunction "IO17_28") (pintype "bidirectional"))
    )
    (net (code "184") (name "unconnected-(U1-IO18-Pad30)") (class "Default")
      (node (ref "U1") (pin "30") (pinfunction "IO18_30") (pintype "bidirectional"))
    )
    (net (code "185") (name "unconnected-(U1-IO19-Pad31)") (class "Default")
      (node (ref "U1") (pin "31") (pinfunction "IO19_31") (pintype "bidirectional"))
    )
    (net (code "186") (name "unconnected-(U1-IO23-Pad37)") (class "Default")
      (node (ref "U1") (pin "37") (pinfunction "IO23_37") (pintype "bidirectional"))
    )
    (net (code "187") (name "unconnected-(U1-IO25-Pad10)") (class "Default")
      (node (ref "U1") (pin "10") (pinfunction "IO25_10") (pintype "bidirectional"))
    )
    (net (code "188") (name "unconnected-(U1-IO26-Pad11)") (class "Default")
      (node (ref "U1") (pin "11") (pinfunction "IO26_11") (pintype "bidirectional"))
    )
    (net (code "189") (name "unconnected-(U1-IO27-Pad12)") (class "Default")
      (node (ref "U1") (pin "12") (pinfunction "IO27_12") (pintype "bidirectional"))
    )
    (net (code "190") (name "unconnected-(U1-IO32-Pad8)") (class "Default")
      (node (ref "U1") (pin "8") (pinfunction "IO32_8") (pintype "bidirectional"))
    )
    (net (code "191") (name "unconnected-(U1-IO33-Pad9)") (class "Default")
      (node (ref "U1") (pin "9") (pinfunction "IO33_9") (pintype "bidirectional"))
    )
    (net (code "192") (name "unconnected-(U1-IO34-Pad6)") (class "Default")
      (node (ref "U1") (pin "6") (pinfunction "IO34_6") (pintype "bidirectional"))
    )
    (net (code "193") (name "unconnected-(U1-IO35-Pad7)") (class "Default")
      (node (ref "U1") (pin "7") (pinfunction "IO35_7") (pintype "bidirectional"))
    )
    (net (code "194") (name "unconnected-(U1-SCL{slash}CLK-Pad20)") (class "Default")
      (node (ref "U1") (pin "20") (pinfunction "SCL/CLK_20") (pintype "bidirectional"))
    )
    (net (code "195") (name "unconnected-(U1-SCS{slash}CMD-Pad19)") (class "Default")
      (node (ref "U1") (pin "19") (pinfunction "SCS/CMD_19") (pintype "bidirectional"))
    )
    (net (code "196") (name "unconnected-(U1-SDI{slash}SD1-Pad22)") (class "Default")
      (node (ref "U1") (pin "22") (pinfunction "SDI/SD1_22") (pintype "bidirectional"))
    )
    (net (code "197") (name "unconnected-(U1-SDO{slash}SD0-Pad21)") (class "Default")
      (node (ref "U1") (pin "21") (pinfunction "SDO/SD0_21") (pintype "bidirectional"))
    )
    (net (code "198") (name "unconnected-(U1-SENSOR_VN-Pad5)") (class "Default")
      (node (ref "U1") (pin "5") (pinfunction "SENSOR_VN_5") (pintype "input"))
    )
    (net (code "199") (name "unconnected-(U1-SENSOR_VP-Pad4)") (class "Default")
      (node (ref "U1") (pin "4") (pinfunction "SENSOR_VP_4") (pintype "input"))
    )
    (net (code "200") (name "unconnected-(U1-SHD{slash}SD2-Pad17)") (class "Default")
      (node (ref "U1") (pin "17") (pinfunction "SHD/SD2_17") (pintype "bidirectional"))
    )
    (net (code "201") (name "unconnected-(U1-SWP{slash}SD3-Pad18)") (class "Default")
      (node (ref "U1") (pin "18") (pinfunction "SWP/SD3_18") (pintype "bidirectional"))
    )
    (net (code "202") (name "unconnected-(USB-C-CC1-PadA5)") (class "Default")
      (node (ref "USB-C") (pin "A5") (pinfunction "CC1_A5") (pintype "passive"))
    )
    (net (code "203") (name "unconnected-(USB-C-CC2-PadB5)") (class "Default")
      (node (ref "USB-C") (pin "B5") (pinfunction "CC2_B5") (pintype "passive"))
    )
    (net (code "204") (name "unconnected-(USB-C-RX1+-PadB11)") (class "Default")
      (node (ref "USB-C") (pin "B11") (pinfunction "RX1+_B11") (pintype "passive"))
    )
    (net (code "205") (name "unconnected-(USB-C-RX1--PadB10)") (class "Default")
      (node (ref "USB-C") (pin "B10") (pinfunction "RX1-_B10") (pintype "passive"))
    )
    (net (code "206") (name "unconnected-(USB-C-RX2+-PadA11)") (class "Default")
      (node (ref "USB-C") (pin "A11") (pinfunction "RX2+_A11") (pintype "passive"))
    )
    (net (code "207") (name "unconnected-(USB-C-RX2--PadA10)") (class "Default")
      (node (ref "USB-C") (pin "A10") (pinfunction "RX2-_A10") (pintype "passive"))
    )
    (net (code "208") (name "unconnected-(USB-C-SBU1-PadA8)") (class "Default")
      (node (ref "USB-C") (pin "A8") (pinfunction "SBU1_A8") (pintype "passive"))
    )
    (net (code "209") (name "unconnected-(USB-C-SBU2-PadB8)") (class "Default")
      (node (ref "USB-C") (pin "B8") (pinfunction "SBU2_B8") (pintype "passive"))
    )
    (net (code "210") (name "unconnected-(USB-C-TX1+-PadA2)") (class "Default")
      (node (ref "USB-C") (pin "A2") (pinfunction "TX1+_A2") (pintype "passive"))
    )
    (net (code "211") (name "unconnected-(USB-C-TX1--PadA3)") (class "Default")
      (node (ref "USB-C") (pin "A3") (pinfunction "TX1-_A3") (pintype "passive"))
    )
    (net (code "212") (name "unconnected-(USB-C-TX2+-PadB2)") (class "Default")
      (node (ref "USB-C") (pin "B2") (pinfunction "TX2+_B2") (pintype "passive"))
    )
    (net (code "213") (name "unconnected-(USB-C-TX2--PadB3)") (class "Default")
      (node (ref "USB-C") (pin "B3") (pinfunction "TX2-_B3") (pintype "passive"))
    )
  )
)
